# 3-1.net
KiCad netlist of a schematic drawn in Altium Designer
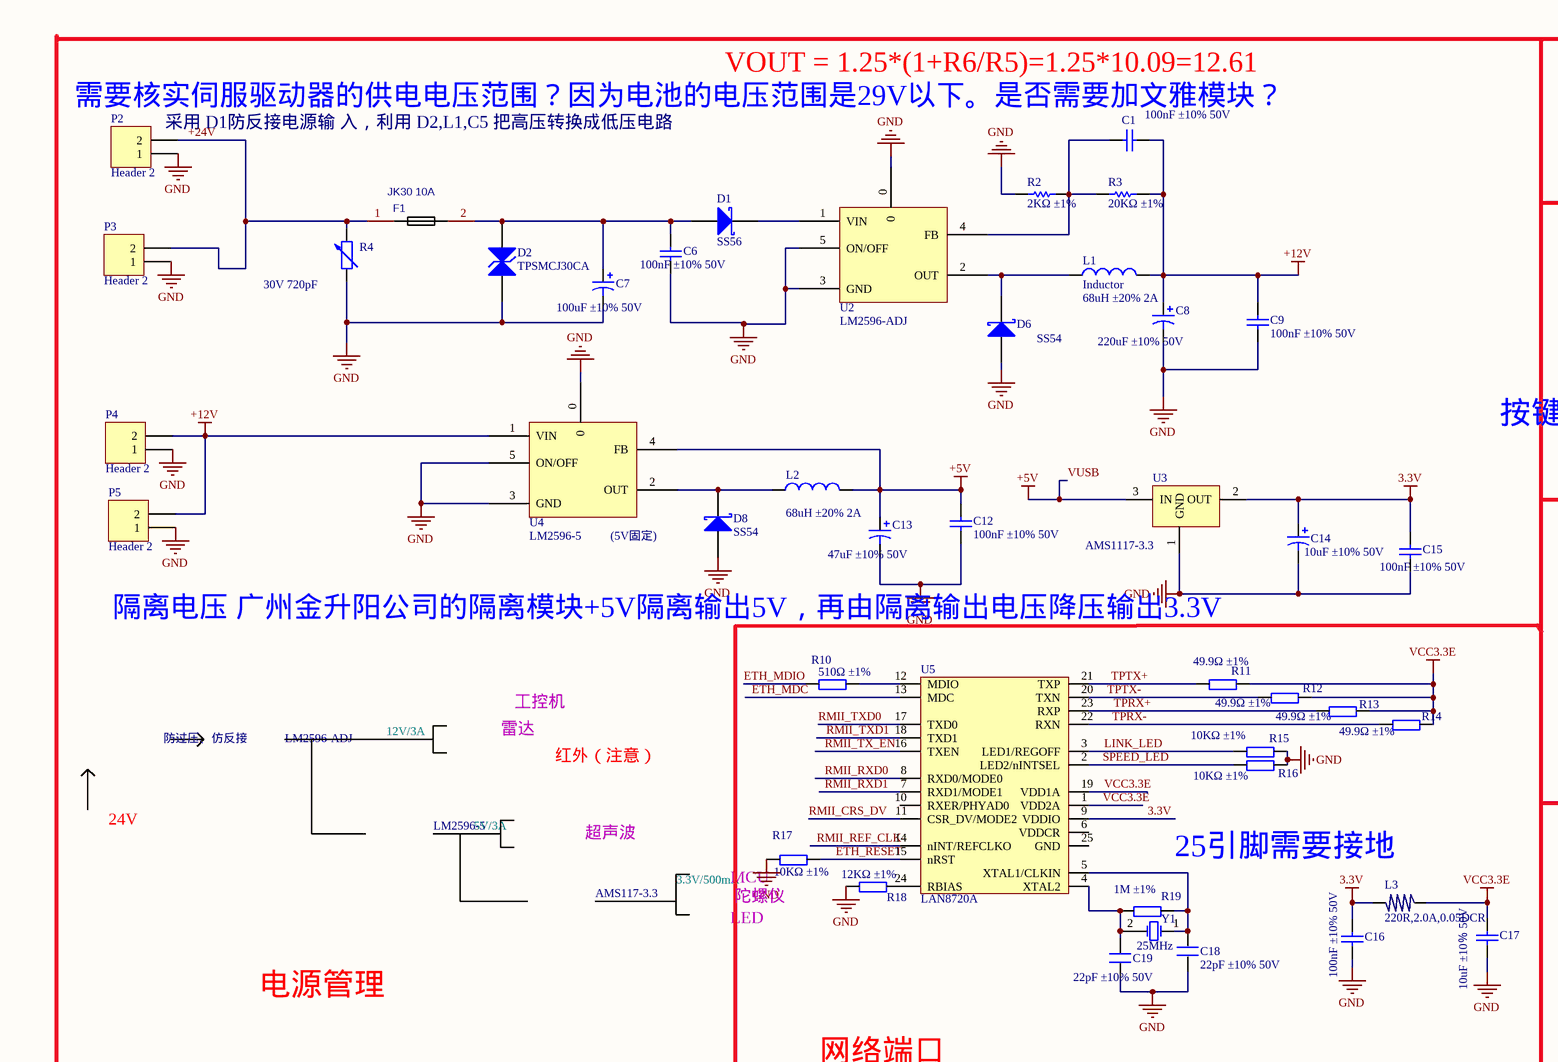
[diagram p0: 运输机器人3-1.SchDoc, top left]
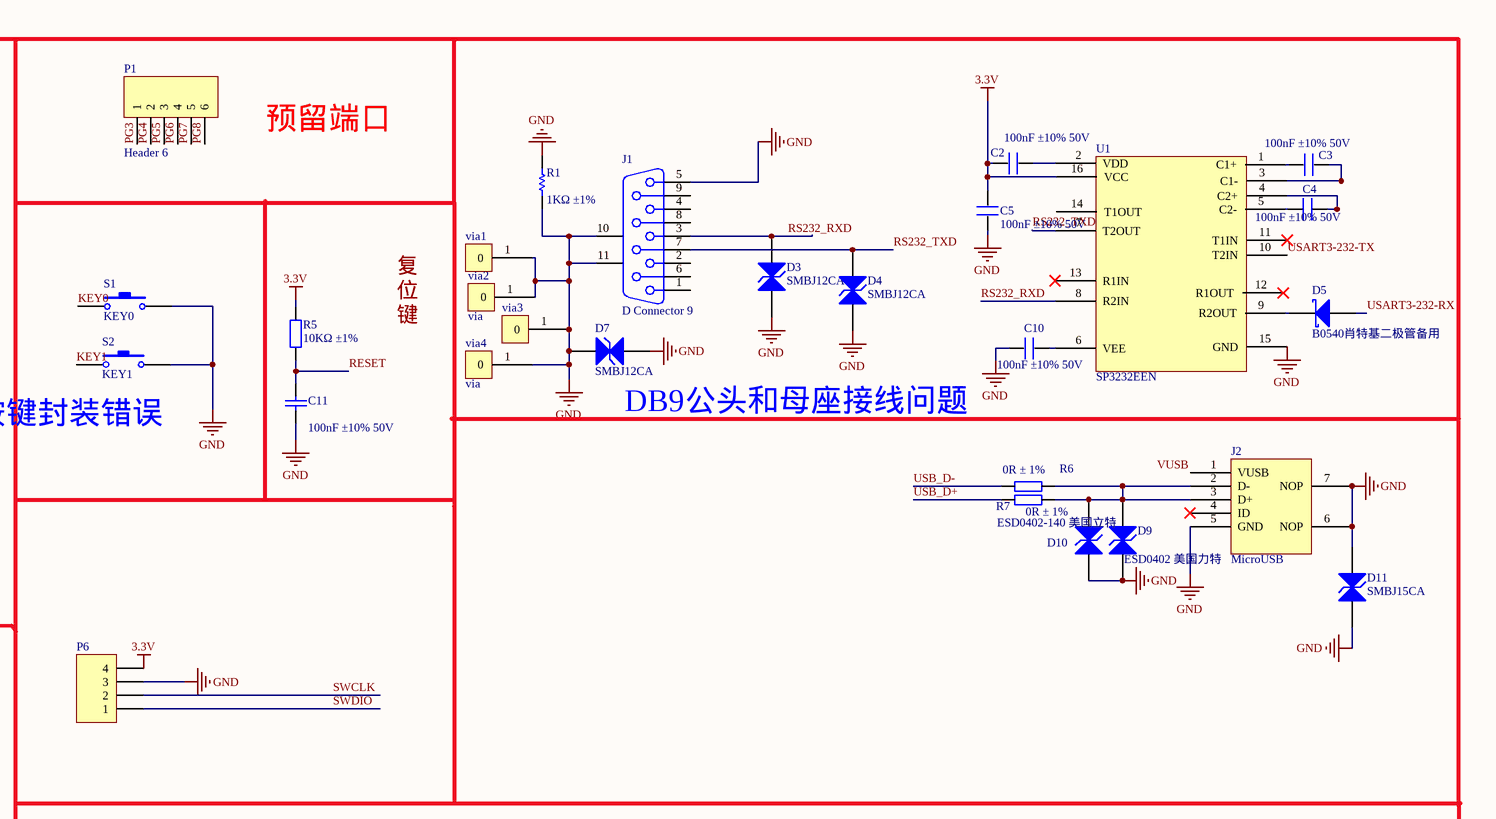
[diagram p1: 运输机器人3-1.SchDoc, top right]
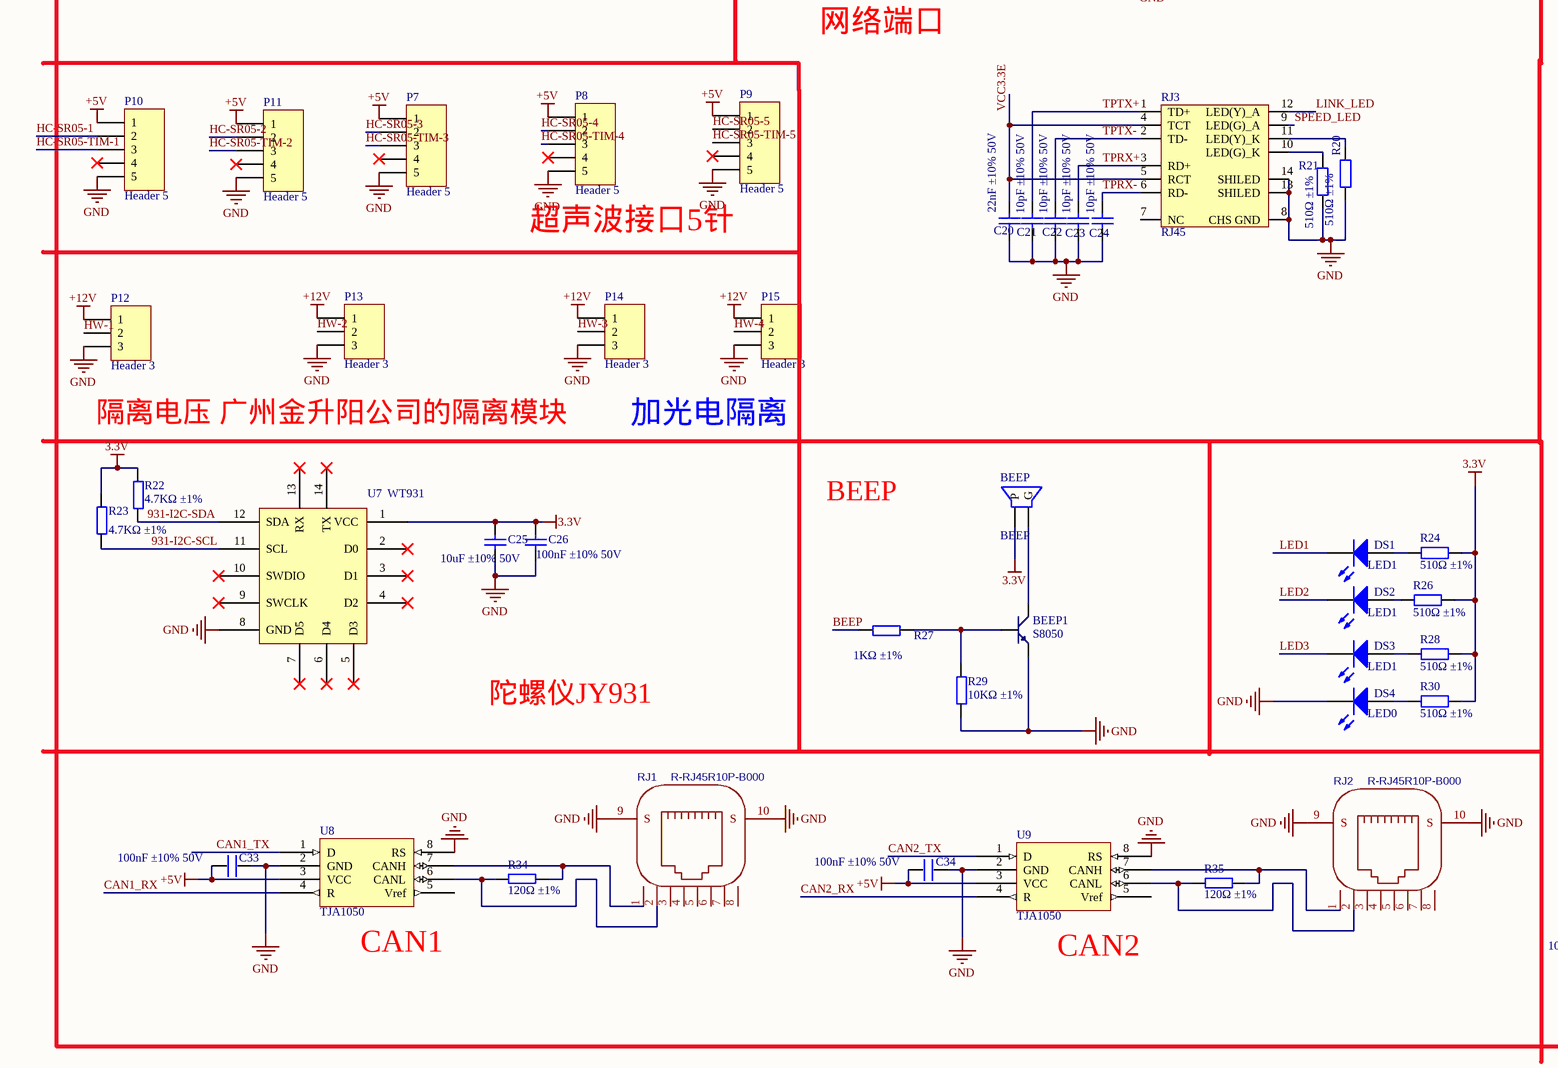
[diagram p2: 运输机器人3-1.SchDoc, bottom left]
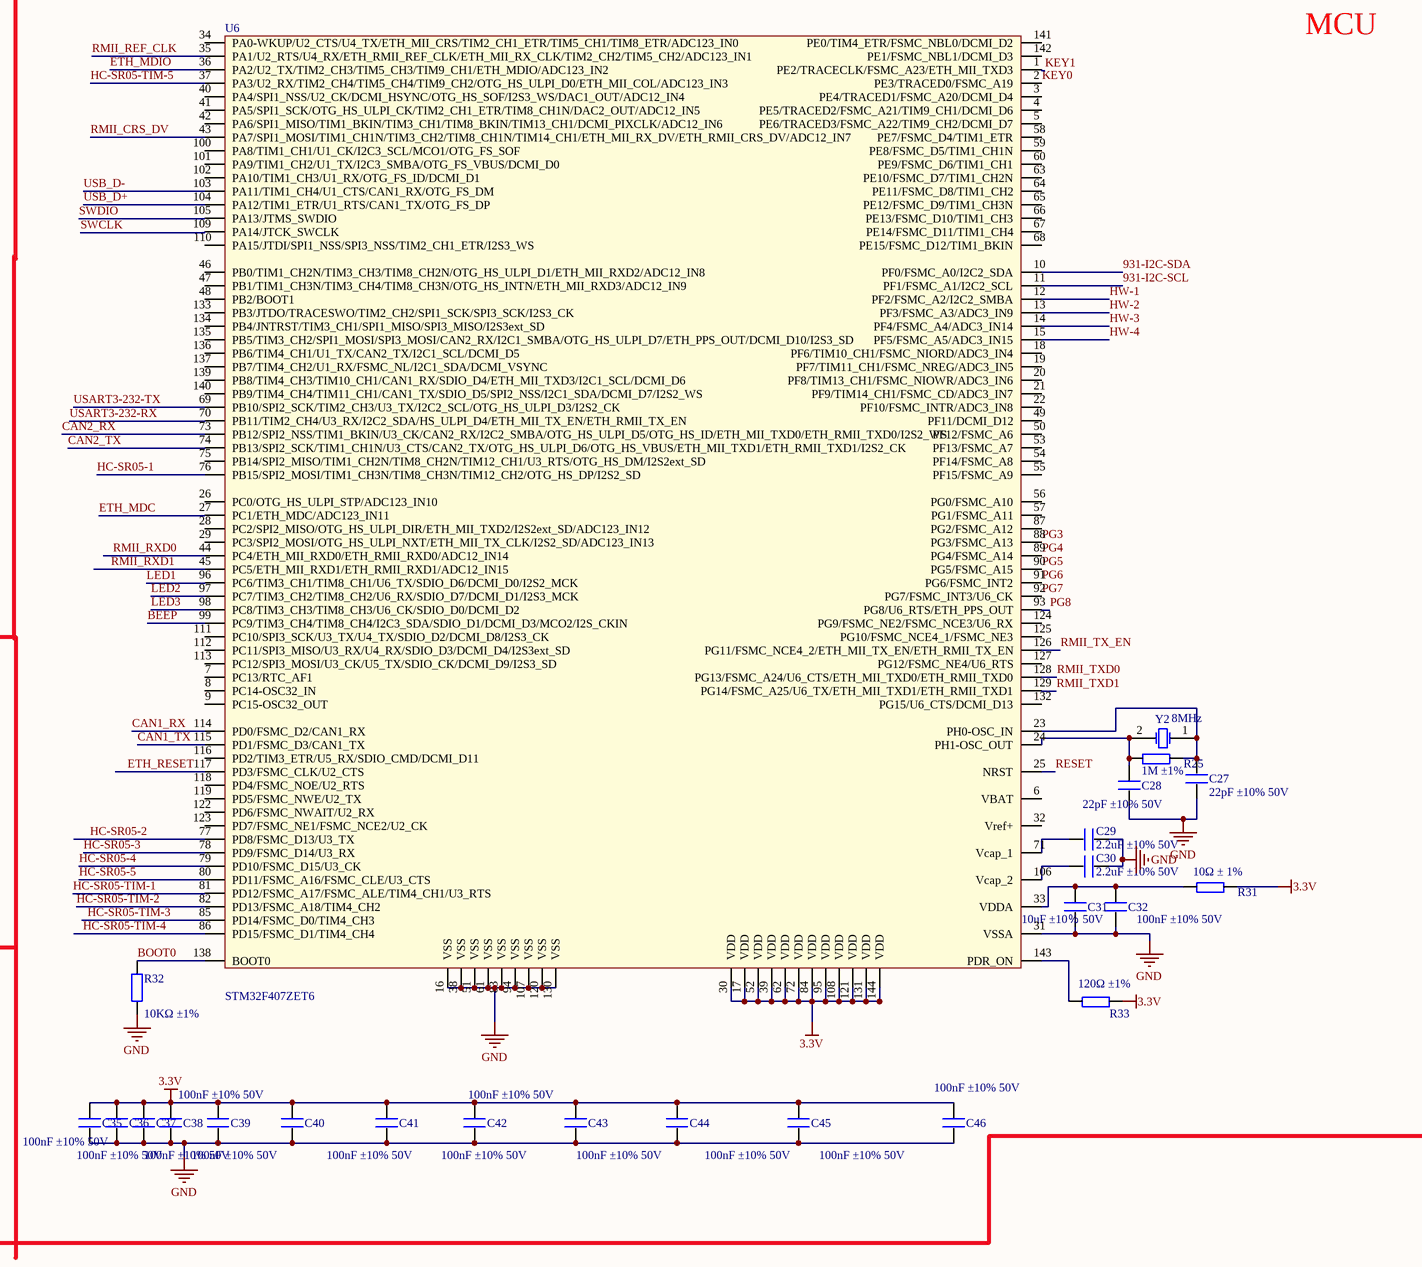
[diagram p3: 运输机器人3-1.SchDoc, bottom right]

(export (version "E")
  (design (tool "Eeschema 10.0.6"))
  (components
    (comp (ref "BEEP")
      (value "BEEP")
      (footprint "LB-BUZ-TH_BD12.0-P7.60-D0.6-FD")
      (libsource (lib "Explorer STM32F407封装库") (part "BEEP"))
    )
    (comp (ref "BEEP1")
      (value "S8050")
      (footprint "LC-SOT-23(SOT-23-3)")
      (description "8050/BCW846/BCW847")
      (libsource (lib "Explorer STM32F407封装库") (part "NPN"))
    )
    (comp (ref "C1")
      (value "100nF ±10% 50V")
      (footprint "LC-0603_C")
      (description "Capacitor")
      (fields (field (name "PUBLISHER") "Altium Limited"))
      (libsource (lib "Miscellaneous Devices") (part "Cap"))
    )
    (comp (ref "C2")
      (value "100nF ±10% 50V")
      (footprint "LC-0603_C")
      (libsource (lib "WarShip V3 STM32103封装库") (part "C"))
    )
    (comp (ref "C3")
      (value "100nF ±10% 50V")
      (footprint "LC-0603_C")
      (libsource (lib "WarShip V3 STM32103封装库") (part "C"))
    )
    (comp (ref "C4")
      (value "100nF ±10% 50V")
      (footprint "LC-0603_C")
      (libsource (lib "WarShip V3 STM32103封装库") (part "C"))
    )
    (comp (ref "C5")
      (value "100nF ±10% 50V")
      (footprint "LC-0603_C")
      (libsource (lib "WarShip V3 STM32103封装库") (part "C"))
    )
    (comp (ref "C6")
      (value "100nF ±10% 50V")
      (footprint "LC-0603_C")
      (description "Capacitor")
      (fields (field (name "PUBLISHER") "Altium Limited"))
      (libsource (lib "Miscellaneous Devices") (part "Cap"))
    )
    (comp (ref "C7")
      (value "100uF ±10% 50V")
      (footprint "C-RB.1/.4 8*12")
      (description "Polarized Capacitor (Radial)")
      (fields (field (name "PUBLISHER") "Altium Limited"))
      (libsource (lib "Miscellaneous Devices") (part "Cap Pol1"))
    )
    (comp (ref "C8")
      (value "220uF ±10% 50V")
      (footprint "C-RB.2/.4 Φ10")
      (description "Polarized Capacitor (Radial)")
      (fields (field (name "PUBLISHER") "Altium Limited"))
      (libsource (lib "Miscellaneous Devices") (part "Cap Pol1"))
    )
    (comp (ref "C9")
      (value "100nF ±10% 50V")
      (footprint "LC-0603_C")
      (description "Capacitor")
      (fields (field (name "PUBLISHER") "Altium Limited"))
      (libsource (lib "Miscellaneous Devices") (part "Cap"))
    )
    (comp (ref "C10")
      (value "100nF ±10% 50V")
      (footprint "LC-0603_C")
      (libsource (lib "WarShip V3 STM32103封装库") (part "C"))
    )
    (comp (ref "C11")
      (value "100nF ±10% 50V")
      (footprint "LC-0603_C")
      (description "Capacitor (Semiconductor SIM Model)")
      (fields (field (name "PUBLISHER") "Altium Limited"))
      (libsource (lib "Miscellaneous Devices") (part "Cap Semi"))
    )
    (comp (ref "C12")
      (value "100nF ±10% 50V")
      (footprint "LC-0603_C")
      (description "Capacitor")
      (fields (field (name "PUBLISHER") "Altium Limited"))
      (libsource (lib "Miscellaneous Devices") (part "Cap"))
    )
    (comp (ref "C13")
      (value "47uF ±10% 50V")
      (footprint "LC-1206_C")
      (description "Polarized Capacitor (Radial)")
      (fields (field (name "PUBLISHER") "Altium Limited"))
      (libsource (lib "Miscellaneous Devices") (part "Cap Pol1"))
    )
    (comp (ref "C14")
      (value "10uF ±10% 50V")
      (footprint "LC-1206_C")
      (description "Polarized Capacitor (Radial)")
      (fields (field (name "PUBLISHER") "Altium Limited"))
      (libsource (lib "Miscellaneous Devices") (part "Cap Pol1"))
    )
    (comp (ref "C15")
      (value "100nF ±10% 50V")
      (footprint "LC-0603_C")
      (description "Capacitor")
      (fields (field (name "PUBLISHER") "Altium Limited"))
      (libsource (lib "Miscellaneous Devices") (part "Cap"))
    )
    (comp (ref "C16")
      (value "100nF ±10% 50V")
      (footprint "LC-0603_C")
      (description "Capacitor")
      (fields (field (name "PUBLISHER") "Altium Limited"))
      (libsource (lib "Miscellaneous Devices") (part "Cap"))
    )
    (comp (ref "C17")
      (value "10uF ±10％ 50V")
      (footprint "LC-1206_C")
      (description "Capacitor")
      (fields (field (name "PUBLISHER") "Altium Limited"))
      (libsource (lib "Miscellaneous Devices") (part "Cap"))
    )
    (comp (ref "C18")
      (value "22pF ±10% 50V")
      (footprint "LC-0603_C")
      (libsource (lib "WarShip V3 STM32103封装库") (part "C"))
    )
    (comp (ref "C19")
      (value "22pF ±10% 50V")
      (footprint "LC-0603_C")
      (libsource (lib "WarShip V3 STM32103封装库") (part "C"))
    )
    (comp (ref "C20")
      (value "22nF ±10% 50V")
      (footprint "LC-0603_C")
      (description "Capacitor")
      (fields (field (name "PUBLISHER") "Altium Limited"))
      (libsource (lib "Miscellaneous Devices") (part "Cap"))
    )
    (comp (ref "C21")
      (value "10pF ±10% 50V")
      (footprint "LC-0603_C")
      (description "Capacitor")
      (fields (field (name "PUBLISHER") "Altium Limited"))
      (libsource (lib "Miscellaneous Devices") (part "Cap"))
    )
    (comp (ref "C22")
      (value "10pF ±10% 50V")
      (footprint "LC-0603_C")
      (description "Capacitor")
      (fields (field (name "PUBLISHER") "Altium Limited"))
      (libsource (lib "Miscellaneous Devices") (part "Cap"))
    )
    (comp (ref "C23")
      (value "10pF ±10% 50V")
      (footprint "LC-0603_C")
      (description "Capacitor")
      (fields (field (name "PUBLISHER") "Altium Limited"))
      (libsource (lib "Miscellaneous Devices") (part "Cap"))
    )
    (comp (ref "C24")
      (value "10pF ±10% 50V")
      (footprint "LC-0603_C")
      (description "Capacitor")
      (fields (field (name "PUBLISHER") "Altium Limited"))
      (libsource (lib "Miscellaneous Devices") (part "Cap"))
    )
    (comp (ref "C25")
      (value "10uF ±10% 50V")
      (footprint "LC-1206_C")
      (description "Capacitor")
      (fields (field (name "PUBLISHER") "Altium Limited"))
      (libsource (lib "Miscellaneous Devices") (part "Cap"))
    )
    (comp (ref "C26")
      (value "100nF ±10% 50V")
      (footprint "LC-0603_C")
      (description "Capacitor")
      (fields (field (name "PUBLISHER") "Altium Limited"))
      (libsource (lib "Miscellaneous Devices") (part "Cap"))
    )
    (comp (ref "C27")
      (value "22pF ±10% 50V")
      (footprint "LC-0603_C")
      (libsource (lib "WarShip V3 STM32103封装库") (part "C"))
    )
    (comp (ref "C28")
      (value "22pF ±10% 50V")
      (footprint "LC-0603_C")
      (libsource (lib "WarShip V3 STM32103封装库") (part "C"))
    )
    (comp (ref "C29")
      (value "2.2uF ±10% 50V")
      (footprint "LC-0603_C")
      (libsource (lib "WarShip V3 STM32103封装库") (part "C"))
    )
    (comp (ref "C30")
      (value "2.2uF ±10% 50V")
      (footprint "LC-0603_C")
      (libsource (lib "WarShip V3 STM32103封装库") (part "C"))
    )
    (comp (ref "C31")
      (value "10uF ±10％ 50V")
      (footprint "LC-1206_C")
      (libsource (lib "WarShip V3 STM32103封装库") (part "C"))
    )
    (comp (ref "C32")
      (value "100nF ±10% 50V")
      (footprint "LC-0603_C")
      (libsource (lib "WarShip V3 STM32103封装库") (part "C"))
    )
    (comp (ref "C33")
      (value "100nF ±10% 50V")
      (footprint "LC-0603_C")
      (libsource (lib "WarShip V3 STM32103封装库") (part "C"))
    )
    (comp (ref "C34")
      (value "100nF ±10% 50V")
      (footprint "LC-0603_C")
      (libsource (lib "WarShip V3 STM32103封装库") (part "C"))
    )
    (comp (ref "C35")
      (value "100nF ±10% 50V")
      (footprint "LC-0603_C")
      (libsource (lib "WarShip V3 STM32103封装库") (part "C"))
    )
    (comp (ref "C36")
      (value "100nF ±10% 50V")
      (footprint "LC-0603_C")
      (libsource (lib "WarShip V3 STM32103封装库") (part "C"))
    )
    (comp (ref "C37")
      (value "100nF ±10% 50V")
      (footprint "LC-0603_C")
      (libsource (lib "WarShip V3 STM32103封装库") (part "C"))
    )
    (comp (ref "C38")
      (value "100nF ±10% 50V")
      (footprint "LC-0603_C")
      (libsource (lib "WarShip V3 STM32103封装库") (part "C"))
    )
    (comp (ref "C39")
      (value "100nF ±10% 50V")
      (footprint "LC-0603_C")
      (libsource (lib "WarShip V3 STM32103封装库") (part "C"))
    )
    (comp (ref "C40")
      (value "100nF ±10% 50V")
      (footprint "LC-0603_C")
      (libsource (lib "WarShip V3 STM32103封装库") (part "C"))
    )
    (comp (ref "C41")
      (value "100nF ±10% 50V")
      (footprint "LC-0603_C")
      (libsource (lib "WarShip V3 STM32103封装库") (part "C"))
    )
    (comp (ref "C42")
      (value "100nF ±10% 50V")
      (footprint "LC-0603_C")
      (libsource (lib "WarShip V3 STM32103封装库") (part "C"))
    )
    (comp (ref "C43")
      (value "100nF ±10% 50V")
      (footprint "LC-0603_C")
      (libsource (lib "WarShip V3 STM32103封装库") (part "C"))
    )
    (comp (ref "C44")
      (value "100nF ±10% 50V")
      (footprint "LC-0603_C")
      (libsource (lib "WarShip V3 STM32103封装库") (part "C"))
    )
    (comp (ref "C45")
      (value "100nF ±10% 50V")
      (footprint "LC-0603_C")
      (libsource (lib "WarShip V3 STM32103封装库") (part "C"))
    )
    (comp (ref "C46")
      (value "100nF ±10% 50V")
      (footprint "LC-0603_C")
      (libsource (lib "WarShip V3 STM32103封装库") (part "C"))
    )
    (comp (ref "D1")
      (value "SS56")
      (footprint "LC-SMC(DO-214AB)_S2")
      (description "Schottky Diode")
      (fields (field (name "PUBLISHER") "Altium Limited"))
      (libsource (lib "Miscellaneous Devices") (part "D Schottky"))
    )
    (comp (ref "D2")
      (value "TPSMCJ30CA")
      (footprint "LC-SMC(DO-214AB)_S4")
      (description "Zener Diode")
      (fields (field (name "PUBLISHER") "Altium Limited"))
      (libsource (lib "*") (part "D Zener"))
    )
    (comp (ref "D3")
      (value "SMBJ12CA")
      (footprint "LC-SMB(DO-214AA)_S4")
      (description "Zener Diode")
      (fields (field (name "PUBLISHER") "Altium Limited"))
      (libsource (lib "Schlib1") (part "D Zener"))
    )
    (comp (ref "D4")
      (value "SMBJ12CA")
      (footprint "LC-SMB(DO-214AA)_S4")
      (description "Zener Diode")
      (fields (field (name "PUBLISHER") "Altium Limited"))
      (libsource (lib "*") (part "D Zener"))
    )
    (comp (ref "D5")
      (value "B0540肖特基二极管备用")
      (footprint "LC-SOD-123")
      (description "Schottky Diode")
      (fields (field (name "PUBLISHER") "Altium Limited"))
      (libsource (lib "Miscellaneous Devices") (part "D Schottky"))
    )
    (comp (ref "D6")
      (value "SS54")
      (footprint "LC-SMB(DO-214AA)_S4")
      (description "Schottky Diode")
      (fields (field (name "PUBLISHER") "Altium Limited"))
      (libsource (lib "Miscellaneous Devices") (part "D Schottky"))
    )
    (comp (ref "D7")
      (value "SMBJ12CA")
      (footprint "LC-SMB(DO-214AA)_S4")
      (description "Zener Diode")
      (fields (field (name "PUBLISHER") "Altium Limited"))
      (libsource (lib "Schlib1") (part "D Zener"))
    )
    (comp (ref "D8")
      (value "SS54")
      (footprint "LC-SMB(DO-214AA)_S4")
      (description "Schottky Diode")
      (fields (field (name "PUBLISHER") "Altium Limited"))
      (libsource (lib "Miscellaneous Devices") (part "D Schottky"))
    )
    (comp (ref "D9")
      (value "ESD0402 美国力特")
      (footprint "LC-0603")
      (description "Zener Diode")
      (fields (field (name "PUBLISHER") "Altium Limited"))
      (libsource (lib "*") (part "D Zener"))
    )
    (comp (ref "D10")
      (value "ESD0402-140 美国立特")
      (footprint "LC-0603")
      (description "Zener Diode")
      (fields (field (name "PUBLISHER") "Altium Limited"))
      (libsource (lib "*") (part "D Zener"))
    )
    (comp (ref "D11")
      (value "SMBJ15CA")
      (footprint "LC-SMB(DO-214AA)_S5")
      (description "Zener Diode")
      (fields (field (name "PUBLISHER") "Altium Limited"))
      (libsource (lib "*") (part "D Zener"))
    )
    (comp (ref "DS1")
      (value "LED1")
      (footprint "LC-0805")
      (description "Typical RED, GREEN, YELLOW, AMBER GaAs LED")
      (fields (field (name "PUBLISHER") "Altium Limited"))
      (libsource (lib "Explorer STM32F407封装库") (part "LED2"))
    )
    (comp (ref "DS2")
      (value "LED1")
      (footprint "LC-0805")
      (description "Typical RED, GREEN, YELLOW, AMBER GaAs LED")
      (fields (field (name "PUBLISHER") "Altium Limited"))
      (libsource (lib "Explorer STM32F407封装库") (part "LED2"))
    )
    (comp (ref "DS3")
      (value "LED1")
      (footprint "LC-0805")
      (description "Typical RED, GREEN, YELLOW, AMBER GaAs LED")
      (fields (field (name "PUBLISHER") "Altium Limited"))
      (libsource (lib "Explorer STM32F407封装库") (part "LED2"))
    )
    (comp (ref "DS4")
      (value "LED0")
      (footprint "LC-0805")
      (description "Typical RED, GREEN, YELLOW, AMBER GaAs LED")
      (fields (field (name "PUBLISHER") "Altium Limited"))
      (libsource (lib "Explorer STM32F407封装库") (part "LED2"))
    )
    (comp (ref "F1")
      (value "JK30 10A")
      (footprint "JK60-110")
      (fields
        (field (name "BOM_MANUFACTURER PART") "Self-healing fuse/HRL30-500")
        (field (name "BOM_SUPPLIER PART") "C14155")
      )
      (libsource (lib "Schlib1") (part "Self-healing fuse/HRL30-500"))
    )
    (comp (ref "J1")
      (value "D Connector 9")
      (footprint "LB-DSUB-TH_DMR-9P")
      (description "Receptacle Assembly, 9 Position, Right Angle")
      (fields (field (name "PUBLISHER") "Altium Limited"))
      (libsource (lib "Miscellaneous Connectors") (part "D Connector 9"))
    )
    (comp (ref "J2")
      (value "MicroUSB")
      (footprint "MicroUSB - 牛角无边")
      (libsource (lib "Motion Controller") (part "MicroUSB"))
    )
    (comp (ref "L1")
      (value "Inductor")
      (footprint "SMDRH63")
      (fields (field (name "ALTIUM_VALUE") "68uH ±20% 2A") (field (name "PUBLISHER") "Altium Limited"))
      (libsource (lib "Miscellaneous Devices") (part "Inductor"))
    )
    (comp (ref "L2")
      (value "68uH ±20% 2A")
      (footprint "SMDRH63")
      (description "Inductor")
      (fields (field (name "PUBLISHER") "Altium Limited"))
      (libsource (lib "Miscellaneous Devices") (part "Inductor"))
    )
    (comp (ref "L3")
      (value "220R,2.0A,0.05DCR")
      (footprint "LC-0805_L")
      (libsource (lib "Explorer STM32F407封装库") (part "L"))
    )
    (comp (ref "P1")
      (value "Header 6")
      (footprint "HDR1X6")
      (description "Header, 6-Pin")
      (fields (field (name "PUBLISHER") "Altium Limited"))
      (libsource (lib "Miscellaneous Connectors") (part "Header 6"))
    )
    (comp (ref "P2")
      (value "Header 2")
      (footprint "LB-XT60PW")
      (description "Header, 2-Pin")
      (fields (field (name "PUBLISHER") "Altium Limited"))
      (libsource (lib "Miscellaneous Connectors") (part "Header 2"))
    )
    (comp (ref "P3")
      (value "Header 2")
      (footprint "LB-XT60PW")
      (description "Header, 2-Pin")
      (fields (field (name "PUBLISHER") "Altium Limited"))
      (libsource (lib "Miscellaneous Connectors") (part "Header 2"))
    )
    (comp (ref "P4")
      (value "Header 2")
      (footprint "LB-CONN-TH_2P-P5.08_WJ2EDGRC-5.08-2P")
      (description "Header, 2-Pin")
      (fields (field (name "PUBLISHER") "Altium Limited"))
      (libsource (lib "Miscellaneous Connectors") (part "Header 2"))
    )
    (comp (ref "P5")
      (value "Header 2")
      (footprint "LB-CONN-TH_2P-P5.08_WJ2EDGRC-5.08-2P")
      (description "Header, 2-Pin")
      (fields (field (name "PUBLISHER") "Altium Limited"))
      (libsource (lib "Miscellaneous Connectors") (part "Header 2"))
    )
    (comp (ref "P6")
      (value "Header 4")
      (footprint "HDR1X4")
      (description "Header, 4-Pin")
      (fields (field (name "PUBLISHER") "Altium Limited"))
      (libsource (lib "mcumotor") (part "Header 4"))
    )
    (comp (ref "P7")
      (value "Header 5")
      (footprint "LB-CONN-TH_5P-P2.50_X8821WR-05S-N0SN")
      (description "Header, 5-Pin")
      (fields (field (name "PUBLISHER") "Altium Limited"))
      (libsource (lib "Miscellaneous Connectors") (part "Header 5"))
    )
    (comp (ref "P8")
      (value "Header 5")
      (footprint "LB-CONN-TH_5P-P2.50_X8821WR-05S-N0SN")
      (description "Header, 5-Pin")
      (fields (field (name "PUBLISHER") "Altium Limited"))
      (libsource (lib "Miscellaneous Connectors") (part "Header 5"))
    )
    (comp (ref "P9")
      (value "Header 5")
      (footprint "LB-CONN-TH_5P-P2.50_X8821WR-05S-N0SN")
      (description "Header, 5-Pin")
      (fields (field (name "PUBLISHER") "Altium Limited"))
      (libsource (lib "Miscellaneous Connectors") (part "Header 5"))
    )
    (comp (ref "P10")
      (value "Header 5")
      (footprint "LB-CONN-TH_5P-P2.50_X8821WR-05S-N0SN")
      (description "Header, 5-Pin")
      (fields (field (name "PUBLISHER") "Altium Limited"))
      (libsource (lib "Miscellaneous Connectors") (part "Header 5"))
    )
    (comp (ref "P11")
      (value "Header 5")
      (footprint "LB-CONN-TH_5P-P2.50_X8821WR-05S-N0SN")
      (description "Header, 5-Pin")
      (fields (field (name "PUBLISHER") "Altium Limited"))
      (libsource (lib "Miscellaneous Connectors") (part "Header 5"))
    )
    (comp (ref "P12")
      (value "Header 3")
      (footprint "LB-CONN-TH_3P-P2.50_X8821WR-03S-N0SN")
      (description "Header, 3-Pin")
      (fields (field (name "PUBLISHER") "Altium Limited"))
      (libsource (lib "Miscellaneous Connectors") (part "Header 3"))
    )
    (comp (ref "P13")
      (value "Header 3")
      (footprint "LB-CONN-TH_3P-P2.50_X8821WR-03S-N0SN")
      (description "Header, 3-Pin")
      (fields (field (name "PUBLISHER") "Altium Limited"))
      (libsource (lib "Miscellaneous Connectors") (part "Header 3"))
    )
    (comp (ref "P14")
      (value "Header 3")
      (footprint "LB-CONN-TH_3P-P2.50_X8821WR-03S-N0SN")
      (description "Header, 3-Pin")
      (fields (field (name "PUBLISHER") "Altium Limited"))
      (libsource (lib "Miscellaneous Connectors") (part "Header 3"))
    )
    (comp (ref "P15")
      (value "Header 3")
      (footprint "LB-CONN-TH_3P-P2.50_X8821WR-03S-N0SN")
      (description "Header, 3-Pin")
      (fields (field (name "PUBLISHER") "Altium Limited"))
      (libsource (lib "Miscellaneous Connectors") (part "Header 3"))
    )
    (comp (ref "R1")
      (value "1KΩ ±1%")
      (footprint "LC-0603_R")
      (description "Resistor")
      (fields (field (name "PUBLISHER") "Altium Limited"))
      (libsource (lib "Miscellaneous Devices") (part "Res1"))
    )
    (comp (ref "R2")
      (value "2KΩ ±1%")
      (footprint "LC-0603_R")
      (description "Resistor")
      (fields (field (name "PUBLISHER") "Altium Limited"))
      (libsource (lib "Miscellaneous Devices") (part "Res1"))
    )
    (comp (ref "R3")
      (value "20KΩ ±1%")
      (footprint "LC-0603_R")
      (description "Resistor")
      (fields (field (name "PUBLISHER") "Altium Limited"))
      (libsource (lib "Miscellaneous Devices") (part "Res1"))
    )
    (comp (ref "R4")
      (value "30V 720pF")
      (footprint "R-7.5")
      (description "Variable Resistor")
      (fields (field (name "PUBLISHER") "Altium Limited"))
      (libsource (lib "Miscellaneous Devices") (part "Res Adj2"))
    )
    (comp (ref "R5")
      (value "10KΩ ±1%")
      (footprint "LC-0603_R")
      (description "贴片电阻")
      (fields (field (name "版权归属") "源创客"))
      (libsource (lib "PCB_Project1") (part "R"))
    )
    (comp (ref "R6")
      (value "0R ± 1%")
      (footprint "LC-0603_R")
      (libsource (lib "WarShip V3 STM32103封装库") (part "R"))
    )
    (comp (ref "R7")
      (value "0R ± 1%")
      (footprint "LC-0603_R")
      (libsource (lib "WarShip V3 STM32103封装库") (part "R"))
    )
    (comp (ref "R10")
      (value "510Ω ±1%")
      (footprint "LC-0603_R")
      (libsource (lib "WarShip V3 STM32103封装库") (part "R"))
    )
    (comp (ref "R11")
      (value "49.9Ω ±1%")
      (footprint "LC-0603_R")
      (libsource (lib "WarShip V3 STM32103封装库") (part "R"))
    )
    (comp (ref "R12")
      (value "49.9Ω ±1%")
      (footprint "LC-0603_R")
      (libsource (lib "WarShip V3 STM32103封装库") (part "R"))
    )
    (comp (ref "R13")
      (value "49.9Ω ±1%")
      (footprint "LC-0603_R")
      (libsource (lib "WarShip V3 STM32103封装库") (part "R"))
    )
    (comp (ref "R14")
      (value "49.9Ω ±1%")
      (footprint "LC-0603_R")
      (libsource (lib "WarShip V3 STM32103封装库") (part "R"))
    )
    (comp (ref "R15")
      (value "10KΩ ±1%")
      (footprint "LC-0603_R")
      (libsource (lib "WarShip V3 STM32103封装库") (part "R"))
    )
    (comp (ref "R16")
      (value "10KΩ ±1%")
      (footprint "LC-0603_R")
      (libsource (lib "WarShip V3 STM32103封装库") (part "R"))
    )
    (comp (ref "R17")
      (value "10KΩ ±1%")
      (footprint "LC-0603_R")
      (libsource (lib "WarShip V3 STM32103封装库") (part "R"))
    )
    (comp (ref "R18")
      (value "12KΩ ±1%")
      (footprint "LC-0603_R")
      (libsource (lib "WarShip V3 STM32103封装库") (part "R"))
    )
    (comp (ref "R19")
      (value "1M ±1%")
      (footprint "LC-0603_R")
      (libsource (lib "WarShip V3 STM32103封装库") (part "R"))
    )
    (comp (ref "R20")
      (value "510Ω ±1%")
      (footprint "LC-0603_R")
      (description "贴片电阻")
      (fields (field (name "版权归属") "源创客"))
      (libsource (lib "PCB_Project1") (part "R"))
    )
    (comp (ref "R21")
      (value "510Ω ±1%")
      (footprint "LC-0603_R")
      (description "贴片电阻")
      (fields (field (name "版权归属") "源创客"))
      (libsource (lib "PCB_Project1") (part "R"))
    )
    (comp (ref "R22")
      (value "4.7KΩ ±1%")
      (footprint "LC-0603_R")
      (libsource (lib "WarShip V3 STM32103封装库") (part "R"))
    )
    (comp (ref "R23")
      (value "4.7KΩ ±1%")
      (footprint "LC-0603_R")
      (libsource (lib "WarShip V3 STM32103封装库") (part "R"))
    )
    (comp (ref "R24")
      (value "510Ω ±1%")
      (footprint "LC-0603_R")
      (description "贴片电阻")
      (fields (field (name "版权归属") "源创客"))
      (libsource (lib "PCB_Project1") (part "R"))
    )
    (comp (ref "R25")
      (value "1M ±1%")
      (footprint "LC-0603_R")
      (libsource (lib "WarShip V3 STM32103封装库") (part "R"))
    )
    (comp (ref "R26")
      (value "510Ω ±1%")
      (footprint "LC-0603_R")
      (description "贴片电阻")
      (fields (field (name "版权归属") "源创客"))
      (libsource (lib "PCB_Project1") (part "R"))
    )
    (comp (ref "R27")
      (value "1KΩ ±1%")
      (footprint "LC-0603_R")
      (libsource (lib "WarShip V3 STM32103封装库") (part "R"))
    )
    (comp (ref "R28")
      (value "510Ω ±1%")
      (footprint "LC-0603_R")
      (description "贴片电阻")
      (fields (field (name "版权归属") "源创客"))
      (libsource (lib "PCB_Project1") (part "R"))
    )
    (comp (ref "R29")
      (value "10KΩ ±1%")
      (footprint "LC-0603_R")
      (libsource (lib "WarShip V3 STM32103封装库") (part "R"))
    )
    (comp (ref "R30")
      (value "510Ω ±1%")
      (footprint "LC-0603_R")
      (description "贴片电阻")
      (fields (field (name "版权归属") "源创客"))
      (libsource (lib "PCB_Project1") (part "R"))
    )
    (comp (ref "R31")
      (value "10Ω ± 1%")
      (footprint "LC-0603_R")
      (libsource (lib "WarShip V3 STM32103封装库") (part "R"))
    )
    (comp (ref "R32")
      (value "10KΩ ±1%")
      (footprint "LC-0603_R")
      (description "贴片电阻")
      (fields (field (name "版权归属") "源创客"))
      (libsource (lib "PCB_Project1") (part "R"))
    )
    (comp (ref "R33")
      (value "120Ω ±1%")
      (footprint "LC-0603_R")
      (libsource (lib "WarShip V3 STM32103封装库") (part "R"))
    )
    (comp (ref "R34")
      (value "120Ω ±1%")
      (footprint "LC-0603_R")
      (libsource (lib "WarShip V3 STM32103封装库") (part "R"))
    )
    (comp (ref "R35")
      (value "120Ω ±1%")
      (footprint "LC-0603_R")
      (libsource (lib "WarShip V3 STM32103封装库") (part "R"))
    )
    (comp (ref "RJ1")
      (value "R-RJ45R10P-B000")
      (footprint "LB-RJ45-TH_R-RJ45R10P-B000")
      (fields (field (name "BOM_SUPPLIER PART") "C386758") (field (name "CONTRIBUTOR") "LCSC"))
      (libsource (lib "Schlib1") (part "R-RJ45R10P-B000"))
    )
    (comp (ref "RJ2")
      (value "R-RJ45R10P-B000")
      (footprint "LB-RJ45-TH_R-RJ45R10P-B000")
      (fields (field (name "BOM_SUPPLIER PART") "C386758") (field (name "CONTRIBUTOR") "LCSC"))
      (libsource (lib "Schlib1") (part "R-RJ45R10P-B000"))
    )
    (comp (ref "RJ3")
      (value "RJ45")
      (footprint "LB-HR911105A")
      (libsource (lib "Explorer STM32F407封装库") (part "HR911105"))
    )
    (comp (ref "S1")
      (value "KEY0")
      (footprint "LB-SW-TH_4P-L6.0-W6.0-P4.50-LS6.5")
      (description "Switch")
      (fields (field (name "PUBLISHER") "Altium Limited"))
      (libsource (lib "Miscellaneous Devices") (part "SW-PB"))
    )
    (comp (ref "S2")
      (value "KEY1")
      (footprint "LB-SW-TH_4P-L6.0-W6.0-P4.50-LS6.5")
      (description "Switch")
      (fields (field (name "PUBLISHER") "Altium Limited"))
      (libsource (lib "Miscellaneous Devices") (part "SW-PB"))
    )
    (comp (ref "U1")
      (value "SP3232EEN")
      (footprint "LC-SOIC-16_150mil")
      (libsource (lib "Schlib1") (part "SP3232EEN"))
    )
    (comp (ref "U2")
      (value "LM2596-ADJ")
      (footprint "LC-TO-263-5")
      (libsource (lib "伦库") (part "LM2596-ADJ"))
    )
    (comp (ref "U3")
      (value "AMS1117-3.3")
      (footprint "LC-SOT-223")
      (libsource (lib "mcumotor") (part "LM1084"))
    )
    (comp (ref "U4") (value "LM2596-5") (footprint "LC-TO-263-5") (libsource (lib "伦库") (part "LM2596-ADJ")))
    (comp (ref "U5")
      (value "LAN8720A")
      (footprint "LC-QFN-24_4x4x05P")
      (description "ETH PHY")
      (libsource (lib "Explorer STM32F407封装库") (part "LAN8720"))
    )
    (comp (ref "U6")
      (value "STM32F407ZET6")
      (footprint "LC-LQFP-144_20x20x05P")
      (libsource (lib "Explorer STM32F407封装库") (part "STM32F407ZET6"))
    )
    (comp (ref "U7") (value "WT931") (footprint "LB-WT931") (libsource (lib "Schlib1") (part "WT931")))
    (comp (ref "U8")
      (value "TJA1050")
      (footprint "LC-SOIC-8_150mil")
      (libsource (lib "WarShip V3 STM32103封装库") (part "SN65HVD230D"))
    )
    (comp (ref "U9")
      (value "TJA1050")
      (footprint "LC-SOIC-8_150mil")
      (libsource (lib "WarShip V3 STM32103封装库") (part "SN65HVD230D"))
    )
    (comp (ref "via1") (value "via") (footprint "hole") (libsource (lib "Schlib1") (part "via")))
    (comp (ref "via2") (value "via") (footprint "hole") (libsource (lib "Schlib1") (part "via")))
    (comp (ref "via3") (value "via") (footprint "hole") (libsource (lib "Schlib1") (part "via")))
    (comp (ref "via4") (value "via") (footprint "hole") (libsource (lib "Schlib1") (part "via")))
    (comp (ref "Y1")
      (value "25MHz")
      (footprint "LC-HC-49S")
      (description "Crystal Oscillator")
      (fields (field (name "PUBLISHER") "Altium Limited"))
      (libsource (lib "Explorer STM32F407封装库") (part "XTAL"))
    )
    (comp (ref "Y2")
      (value "8MHz")
      (footprint "LC-HC-49S")
      (description "Crystal Oscillator")
      (fields (field (name "PUBLISHER") "Altium Limited"))
      (libsource (lib "Explorer STM32F407封装库") (part "XTAL"))
    )
  )
  (nets
    (net (code "1") (name "+5V") (class "Default")
      (node (ref "C12") (pin "2") (pinfunction "2_2") (pintype "passive"))
      (node (ref "C13") (pin "1") (pinfunction "1_1") (pintype "passive"))
      (node (ref "C33") (pin "1") (pintype "passive"))
      (node (ref "C34") (pin "1") (pintype "passive"))
      (node (ref "J2") (pin "1") (pinfunction "VUSB_1") (pintype "passive"))
      (node (ref "L2") (pin "2") (pinfunction "2_2") (pintype "passive"))
      (node (ref "P10") (pin "1") (pinfunction "1_1") (pintype "passive"))
      (node (ref "P11") (pin "1") (pinfunction "1_1") (pintype "passive"))
      (node (ref "P7") (pin "1") (pinfunction "1_1") (pintype "passive"))
      (node (ref "P8") (pin "1") (pinfunction "1_1") (pintype "passive"))
      (node (ref "P9") (pin "1") (pinfunction "1_1") (pintype "passive"))
      (node (ref "U3") (pin "3") (pinfunction "IN_3") (pintype "passive"))
      (node (ref "U4") (pin "4") (pinfunction "FB_4") (pintype "passive"))
      (node (ref "U8") (pin "3") (pinfunction "VCC_3") (pintype "power_in"))
      (node (ref "U9") (pin "3") (pinfunction "VCC_3") (pintype "power_in"))
    )
    (net (code "2") (name "+12V") (class "Default")
      (node (ref "C1") (pin "2") (pinfunction "2_2") (pintype "passive"))
      (node (ref "C8") (pin "1") (pinfunction "1_1") (pintype "passive"))
      (node (ref "C9") (pin "2") (pinfunction "2_2") (pintype "passive"))
      (node (ref "L1") (pin "2") (pinfunction "2_2") (pintype "passive"))
      (node (ref "P12") (pin "1") (pinfunction "1_1") (pintype "passive"))
      (node (ref "P13") (pin "1") (pinfunction "1_1") (pintype "passive"))
      (node (ref "P14") (pin "1") (pinfunction "1_1") (pintype "passive"))
      (node (ref "P15") (pin "1") (pinfunction "1_1") (pintype "passive"))
      (node (ref "P4") (pin "2") (pinfunction "2_2") (pintype "passive"))
      (node (ref "P5") (pin "2") (pinfunction "2_2") (pintype "passive"))
      (node (ref "R3") (pin "2") (pinfunction "2_2") (pintype "passive"))
      (node (ref "U4") (pin "1") (pinfunction "VIN_1") (pintype "passive"))
    )
    (net (code "3") (name "/+24V") (class "Default")
      (node (ref "F1") (pin "1") (pinfunction "1_1") (pintype "passive"))
      (node (ref "P2") (pin "2") (pinfunction "2_2") (pintype "passive"))
      (node (ref "P3") (pin "2") (pinfunction "2_2") (pintype "passive"))
      (node (ref "R4") (pin "2") (pinfunction "2_2") (pintype "passive"))
    )
    (net (code "4") (name "/931-I2C-SCL") (class "Default")
      (node (ref "R23") (pin "1") (pintype "passive"))
      (node (ref "U6") (pin "11") (pinfunction "PF1/FSMC_A1/I2C2_SCL_11") (pintype "passive"))
      (node (ref "U7") (pin "11") (pinfunction "SCL_11") (pintype "passive"))
    )
    (net (code "5") (name "/931-I2C-SDA") (class "Default")
      (node (ref "R22") (pin "1") (pintype "passive"))
      (node (ref "U6") (pin "10") (pinfunction "PF0/FSMC_A0/I2C2_SDA_10") (pintype "passive"))
      (node (ref "U7") (pin "12") (pinfunction "SDA_12") (pintype "passive"))
    )
    (net (code "6") (name "/BEEP") (class "Default")
      (node (ref "R27") (pin "1") (pintype "passive"))
      (node (ref "U6") (pin "99") (pinfunction "PC9/TIM3_CH4/TIM8_CH4/I2C3_SDA/SDIO_D1/DCMI_D3/MCO2/I2S_CKIN_99") (pintype "passive"))
    )
    (net (code "7") (name "/BOOT0") (class "Default")
      (node (ref "R32") (pin "2") (pinfunction "2_2") (pintype "passive"))
      (node (ref "U6") (pin "138") (pinfunction "BOOT0_138") (pintype "passive"))
    )
    (net (code "8") (name "/CAN1_RX") (class "Default")
      (node (ref "U6") (pin "114") (pinfunction "PD0/FSMC_D2/CAN1_RX_114") (pintype "passive"))
      (node (ref "U8") (pin "4") (pinfunction "R_4") (pintype "output"))
    )
    (net (code "9") (name "/CAN1_TX") (class "Default")
      (node (ref "U6") (pin "115") (pinfunction "PD1/FSMC_D3/CAN1_TX_115") (pintype "passive"))
      (node (ref "U8") (pin "1") (pinfunction "D_1") (pintype "input"))
    )
    (net (code "10") (name "/CAN2_RX") (class "Default")
      (node (ref "U6") (pin "73") (pinfunction "PB12/SPI2_NSS/TIM1_BKIN/U3_CK/CAN2_RX/I2C2_SMBA/OTG_HS_ULPI_D5/OTG_HS_ID/ETH_MII_TXD0/ETH_RMII_TXD0/I2S2_WS_73") (pintype "passive"))
      (node (ref "U9") (pin "4") (pinfunction "R_4") (pintype "output"))
    )
    (net (code "11") (name "/CAN2_TX") (class "Default")
      (node (ref "U6") (pin "74") (pinfunction "PB13/SPI2_SCK/TIM1_CH1N/U3_CTS/CAN2_TX/OTG_HS_ULPI_D6/OTG_HS_VBUS/ETH_MII_TXD1/ETH_RMII_TXD1/I2S2_CK_74") (pintype "passive"))
      (node (ref "U9") (pin "1") (pinfunction "D_1") (pintype "input"))
    )
    (net (code "12") (name "/ETH_MDC") (class "Default")
      (node (ref "U5") (pin "13") (pinfunction "MDC_13") (pintype "passive"))
      (node (ref "U6") (pin "27") (pinfunction "PC1/ETH_MDC/ADC123_IN11_27") (pintype "passive"))
    )
    (net (code "13") (name "/ETH_MDIO") (class "Default")
      (node (ref "R10") (pin "1") (pintype "passive"))
      (node (ref "U6") (pin "36") (pinfunction "PA2/U2_TX/TIM2_CH3/TIM5_CH3/TIM9_CH1/ETH_MDIO/ADC123_IN2_36") (pintype "passive"))
    )
    (net (code "14") (name "/ETH_RESET") (class "Default")
      (node (ref "R17") (pin "2") (pintype "passive"))
      (node (ref "U5") (pin "15") (pinfunction "nRST_15") (pintype "passive"))
      (node (ref "U6") (pin "117") (pinfunction "PD3/FSMC_CLK/U2_CTS_117") (pintype "passive"))
    )
    (net (code "15") (name "/HC-SR05-1") (class "Default")
      (node (ref "P10") (pin "2") (pinfunction "2_2") (pintype "passive"))
      (node (ref "U6") (pin "76") (pinfunction "PB15/SPI2_MOSI/TIM1_CH3N/TIM8_CH3N/TIM12_CH2/OTG_HS_DP/I2S2_SD_76") (pintype "passive"))
    )
    (net (code "16") (name "/HC-SR05-2") (class "Default")
      (node (ref "P11") (pin "2") (pinfunction "2_2") (pintype "passive"))
      (node (ref "U6") (pin "77") (pinfunction "PD8/FSMC_D13/U3_TX_77") (pintype "passive"))
    )
    (net (code "17") (name "/HC-SR05-3") (class "Default")
      (node (ref "P7") (pin "2") (pinfunction "2_2") (pintype "passive"))
      (node (ref "U6") (pin "78") (pinfunction "PD9/FSMC_D14/U3_RX_78") (pintype "passive"))
    )
    (net (code "18") (name "/HC-SR05-4") (class "Default")
      (node (ref "P8") (pin "2") (pinfunction "2_2") (pintype "passive"))
      (node (ref "U6") (pin "79") (pinfunction "PD10/FSMC_D15/U3_CK_79") (pintype "passive"))
    )
    (net (code "19") (name "/HC-SR05-5") (class "Default")
      (node (ref "P9") (pin "2") (pinfunction "2_2") (pintype "passive"))
      (node (ref "U6") (pin "80") (pinfunction "PD11/FSMC_A16/FSMC_CLE/U3_CTS_80") (pintype "passive"))
    )
    (net (code "20") (name "/HC-SR05-TIM-1") (class "Default")
      (node (ref "P10") (pin "3") (pinfunction "3_3") (pintype "passive"))
      (node (ref "U6") (pin "81") (pinfunction "PD12/FSMC_A17/FSMC_ALE/TIM4_CH1/U3_RTS_81") (pintype "passive"))
    )
    (net (code "21") (name "/HC-SR05-TIM-2") (class "Default")
      (node (ref "P11") (pin "3") (pinfunction "3_3") (pintype "passive"))
      (node (ref "U6") (pin "82") (pinfunction "PD13/FSMC_A18/TIM4_CH2_82") (pintype "passive"))
    )
    (net (code "22") (name "/HC-SR05-TIM-3") (class "Default")
      (node (ref "P7") (pin "3") (pinfunction "3_3") (pintype "passive"))
      (node (ref "U6") (pin "85") (pinfunction "PD14/FSMC_D0/TIM4_CH3_85") (pintype "passive"))
    )
    (net (code "23") (name "/HC-SR05-TIM-4") (class "Default")
      (node (ref "P8") (pin "3") (pinfunction "3_3") (pintype "passive"))
      (node (ref "U6") (pin "86") (pinfunction "PD15/FSMC_D1/TIM4_CH4_86") (pintype "passive"))
    )
    (net (code "24") (name "/HC-SR05-TIM-5") (class "Default")
      (node (ref "P9") (pin "3") (pinfunction "3_3") (pintype "passive"))
      (node (ref "U6") (pin "37") (pinfunction "PA3/U2_RX/TIM2_CH4/TIM5_CH4/TIM9_CH2/OTG_HS_ULPI_D0/ETH_MII_COL/ADC123_IN3_37") (pintype "passive"))
    )
    (net (code "25") (name "/HW-1") (class "Default")
      (node (ref "P12") (pin "2") (pinfunction "2_2") (pintype "passive"))
      (node (ref "U6") (pin "12") (pinfunction "PF2/FSMC_A2/I2C2_SMBA_12") (pintype "passive"))
    )
    (net (code "26") (name "/HW-2") (class "Default")
      (node (ref "P13") (pin "2") (pinfunction "2_2") (pintype "passive"))
      (node (ref "U6") (pin "13") (pinfunction "PF3/FSMC_A3/ADC3_IN9_13") (pintype "passive"))
    )
    (net (code "27") (name "/HW-3") (class "Default")
      (node (ref "P14") (pin "2") (pinfunction "2_2") (pintype "passive"))
      (node (ref "U6") (pin "14") (pinfunction "PF4/FSMC_A4/ADC3_IN14_14") (pintype "passive"))
    )
    (net (code "28") (name "/HW-4") (class "Default")
      (node (ref "P15") (pin "2") (pinfunction "2_2") (pintype "passive"))
      (node (ref "U6") (pin "15") (pinfunction "PF5/FSMC_A5/ADC3_IN15_15") (pintype "passive"))
    )
    (net (code "29") (name "/KEY0") (class "Default")
      (node (ref "S1") (pin "1") (pinfunction "1_1") (pintype "passive"))
      (node (ref "U6") (pin "2") (pinfunction "PE3/TRACED0/FSMC_A19_2") (pintype "passive"))
    )
    (net (code "30") (name "/KEY1") (class "Default")
      (node (ref "S2") (pin "1") (pinfunction "1_1") (pintype "passive"))
      (node (ref "U6") (pin "1") (pinfunction "PE2/TRACECLK/FSMC_A23/ETH_MII_TXD3_1") (pintype "passive"))
    )
    (net (code "31") (name "/LED1") (class "Default")
      (node (ref "DS1") (pin "2") (pinfunction "K_2") (pintype "passive"))
      (node (ref "U6") (pin "96") (pinfunction "PC6/TIM3_CH1/TIM8_CH1/U6_TX/SDIO_D6/DCMI_D0/I2S2_MCK_96") (pintype "passive"))
    )
    (net (code "32") (name "/LED2") (class "Default")
      (node (ref "DS2") (pin "2") (pinfunction "K_2") (pintype "passive"))
      (node (ref "U6") (pin "97") (pinfunction "PC7/TIM3_CH2/TIM8_CH2/U6_RX/SDIO_D7/DCMI_D1/I2S3_MCK_97") (pintype "passive"))
    )
    (net (code "33") (name "/LED3") (class "Default")
      (node (ref "DS3") (pin "2") (pinfunction "K_2") (pintype "passive"))
      (node (ref "U6") (pin "98") (pinfunction "PC8/TIM3_CH3/TIM8_CH3/U6_CK/SDIO_D0/DCMI_D2_98") (pintype "passive"))
    )
    (net (code "34") (name "/LINK_LED") (class "Default")
      (node (ref "R15") (pin "1") (pintype "passive"))
      (node (ref "RJ3") (pin "12") (pinfunction "LED(Y)_A_12") (pintype "passive"))
      (node (ref "U5") (pin "3") (pinfunction "LED1/REGOFF_3") (pintype "passive"))
    )
    (net (code "35") (name "/PG3") (class "Default")
      (node (ref "P1") (pin "1") (pinfunction "1_1") (pintype "passive"))
      (node (ref "U6") (pin "88") (pinfunction "PG3/FSMC_A13_88") (pintype "passive"))
    )
    (net (code "36") (name "/PG4") (class "Default")
      (node (ref "P1") (pin "2") (pinfunction "2_2") (pintype "passive"))
      (node (ref "U6") (pin "89") (pinfunction "PG4/FSMC_A14_89") (pintype "passive"))
    )
    (net (code "37") (name "/PG5") (class "Default")
      (node (ref "P1") (pin "3") (pinfunction "3_3") (pintype "passive"))
      (node (ref "U6") (pin "90") (pinfunction "PG5/FSMC_A15_90") (pintype "passive"))
    )
    (net (code "38") (name "/PG6") (class "Default")
      (node (ref "P1") (pin "4") (pinfunction "4_4") (pintype "passive"))
      (node (ref "U6") (pin "91") (pinfunction "PG6/FSMC_INT2_91") (pintype "passive"))
    )
    (net (code "39") (name "/PG7") (class "Default")
      (node (ref "P1") (pin "5") (pinfunction "5_5") (pintype "passive"))
      (node (ref "U6") (pin "92") (pinfunction "PG7/FSMC_INT3/U6_CK_92") (pintype "passive"))
    )
    (net (code "40") (name "/PG8") (class "Default")
      (node (ref "P1") (pin "6") (pinfunction "6_6") (pintype "passive"))
      (node (ref "U6") (pin "93") (pinfunction "PG8/U6_RTS/ETH_PPS_OUT_93") (pintype "passive"))
    )
    (net (code "41") (name "/RESET") (class "Default")
      (node (ref "C11") (pin "2") (pinfunction "2_2") (pintype "passive"))
      (node (ref "R5") (pin "1") (pinfunction "1_1") (pintype "passive"))
      (node (ref "U6") (pin "25") (pinfunction "NRST_25") (pintype "passive"))
    )
    (net (code "42") (name "/RMII_CRS_DV") (class "Default")
      (node (ref "U5") (pin "11") (pinfunction "CSR_DV/MODE2_11") (pintype "passive"))
      (node (ref "U6") (pin "43") (pinfunction "PA7/SPI1_MOSI/TIM1_CH1N/TIM3_CH2/TIM8_CH1N/TIM14_CH1/ETH_MII_RX_DV/ETH_RMII_CRS_DV/ADC12_IN7_43") (pintype "passive"))
    )
    (net (code "43") (name "/RMII_REF_CLK") (class "Default")
      (node (ref "U5") (pin "14") (pinfunction "nINT/REFCLKO_14") (pintype "passive"))
      (node (ref "U6") (pin "35") (pinfunction "PA1/U2_RTS/U4_RX/ETH_RMII_REF_CLK/ETH_MII_RX_CLK/TIM2_CH2/TIM5_CH2/ADC123_IN1_35") (pintype "passive"))
    )
    (net (code "44") (name "/RMII_RXD0") (class "Default")
      (node (ref "U5") (pin "8") (pinfunction "RXD0/MODE0_8") (pintype "passive"))
      (node (ref "U6") (pin "44") (pinfunction "PC4/ETH_MII_RXD0/ETH_RMII_RXD0/ADC12_IN14_44") (pintype "passive"))
    )
    (net (code "45") (name "/RMII_RXD1") (class "Default")
      (node (ref "U5") (pin "7") (pinfunction "RXD1/MODE1_7") (pintype "passive"))
      (node (ref "U6") (pin "45") (pinfunction "PC5/ETH_MII_RXD1/ETH_RMII_RXD1/ADC12_IN15_45") (pintype "passive"))
    )
    (net (code "46") (name "/RMII_TXD0") (class "Default")
      (node (ref "U5") (pin "17") (pinfunction "TXD0_17") (pintype "passive"))
      (node (ref "U6") (pin "128") (pinfunction "PG13/FSMC_A24/U6_CTS/ETH_MII_TXD0/ETH_RMII_TXD0_128") (pintype "passive"))
    )
    (net (code "47") (name "/RMII_TXD1") (class "Default")
      (node (ref "U5") (pin "18") (pinfunction "TXD1_18") (pintype "passive"))
      (node (ref "U6") (pin "129") (pinfunction "PG14/FSMC_A25/U6_TX/ETH_MII_TXD1/ETH_RMII_TXD1_129") (pintype "passive"))
    )
    (net (code "48") (name "/RMII_TX_EN") (class "Default")
      (node (ref "U5") (pin "16") (pinfunction "TXEN_16") (pintype "passive"))
      (node (ref "U6") (pin "126") (pinfunction "PG11/FSMC_NCE4_2/ETH_MII_TX_EN/ETH_RMII_TX_EN_126") (pintype "passive"))
    )
    (net (code "49") (name "/RS232_RXD") (class "Default")
      (node (ref "D3") (pin "2") (pinfunction "K_2") (pintype "passive"))
      (node (ref "J1") (pin "3") (pinfunction "3_3") (pintype "passive"))
      (node (ref "U1") (pin "8") (pinfunction "R2IN_8") (pintype "passive"))
    )
    (net (code "50") (name "/RS232_TXD") (class "Default")
      (node (ref "D4") (pin "2") (pinfunction "K_2") (pintype "passive"))
      (node (ref "J1") (pin "7") (pinfunction "7_7") (pintype "passive"))
      (node (ref "U1") (pin "7") (pinfunction "T2OUT_7") (pintype "passive"))
    )
    (net (code "51") (name "/SPEED_LED") (class "Default")
      (node (ref "R16") (pin "1") (pintype "passive"))
      (node (ref "RJ3") (pin "9") (pinfunction "LED(G)_A_9") (pintype "passive"))
      (node (ref "U5") (pin "2") (pinfunction "LED2/nINTSEL_2") (pintype "passive"))
    )
    (net (code "52") (name "/SWCLK") (class "Default")
      (node (ref "P6") (pin "2") (pinfunction "2_2") (pintype "passive"))
      (node (ref "U6") (pin "109") (pinfunction "PA14/JTCK_SWCLK_109") (pintype "passive"))
    )
    (net (code "53") (name "/SWDIO") (class "Default")
      (node (ref "P6") (pin "1") (pinfunction "1_1") (pintype "passive"))
      (node (ref "U6") (pin "105") (pinfunction "PA13/JTMS_SWDIO_105") (pintype "passive"))
    )
    (net (code "54") (name "/TPRX+") (class "Default")
      (node (ref "C23") (pin "1") (pinfunction "1_1") (pintype "passive"))
      (node (ref "R13") (pin "1") (pintype "passive"))
      (node (ref "RJ3") (pin "3") (pinfunction "RD+_3") (pintype "passive"))
      (node (ref "U5") (pin "23") (pinfunction "RXP_23") (pintype "passive"))
    )
    (net (code "55") (name "/TPRX-") (class "Default")
      (node (ref "C24") (pin "1") (pinfunction "1_1") (pintype "passive"))
      (node (ref "R14") (pin "1") (pintype "passive"))
      (node (ref "RJ3") (pin "6") (pinfunction "RD-_6") (pintype "passive"))
      (node (ref "U5") (pin "22") (pinfunction "RXN_22") (pintype "passive"))
    )
    (net (code "56") (name "/TPTX+") (class "Default")
      (node (ref "C21") (pin "1") (pinfunction "1_1") (pintype "passive"))
      (node (ref "R11") (pin "1") (pintype "passive"))
      (node (ref "RJ3") (pin "1") (pinfunction "TD+_1") (pintype "passive"))
      (node (ref "U5") (pin "21") (pinfunction "TXP_21") (pintype "passive"))
    )
    (net (code "57") (name "/TPTX-") (class "Default")
      (node (ref "C22") (pin "1") (pinfunction "1_1") (pintype "passive"))
      (node (ref "R12") (pin "1") (pintype "passive"))
      (node (ref "RJ3") (pin "2") (pinfunction "TD-_2") (pintype "passive"))
      (node (ref "U5") (pin "20") (pinfunction "TXN_20") (pintype "passive"))
    )
    (net (code "58") (name "/USART3-232-RX") (class "Default")
      (node (ref "D5") (pin "1") (pinfunction "A_1") (pintype "passive"))
      (node (ref "U6") (pin "70") (pinfunction "PB11/TIM2_CH4/U3_RX/I2C2_SDA/HS_ULPI_D4/ETH_MII_TX_EN/ETH_RMII_TX_EN_70") (pintype "passive"))
    )
    (net (code "59") (name "/USART3-232-TX") (class "Default")
      (node (ref "U1") (pin "10") (pinfunction "T2IN_10") (pintype "passive"))
      (node (ref "U6") (pin "69") (pinfunction "PB10/SPI2_SCK/TIM2_CH3/U3_TX/I2C2_SCL/OTG_HS_ULPI_D3/I2S2_CK_69") (pintype "passive"))
    )
    (net (code "60") (name "/USB_D+") (class "Default")
      (node (ref "R7") (pin "1") (pintype "passive"))
      (node (ref "U6") (pin "104") (pinfunction "PA12/TIM1_ETR/U1_RTS/CAN1_TX/OTG_FS_DP_104") (pintype "passive"))
    )
    (net (code "61") (name "/USB_D-") (class "Default")
      (node (ref "R6") (pin "1") (pintype "passive"))
      (node (ref "U6") (pin "103") (pinfunction "PA11/TIM1_CH4/U1_CTS/CAN1_RX/OTG_FS_DM_103") (pintype "passive"))
    )
    (net (code "62") (name "3.3V") (class "Default")
      (node (ref "BEEP") (pin "1") (pinfunction "P_1") (pintype "passive"))
      (node (ref "C14") (pin "1") (pinfunction "1_1") (pintype "passive"))
      (node (ref "C15") (pin "1") (pinfunction "1_1") (pintype "passive"))
      (node (ref "C16") (pin "2") (pinfunction "2_2") (pintype "passive"))
      (node (ref "C2") (pin "2") (pintype "passive"))
      (node (ref "C25") (pin "2") (pinfunction "2_2") (pintype "passive"))
      (node (ref "C26") (pin "2") (pinfunction "2_2") (pintype "passive"))
      (node (ref "C35") (pin "2") (pintype "passive"))
      (node (ref "C36") (pin "2") (pintype "passive"))
      (node (ref "C37") (pin "2") (pintype "passive"))
      (node (ref "C38") (pin "2") (pintype "passive"))
      (node (ref "C39") (pin "2") (pintype "passive"))
      (node (ref "C40") (pin "2") (pintype "passive"))
      (node (ref "C41") (pin "2") (pintype "passive"))
      (node (ref "C42") (pin "2") (pintype "passive"))
      (node (ref "C43") (pin "2") (pintype "passive"))
      (node (ref "C44") (pin "2") (pintype "passive"))
      (node (ref "C45") (pin "2") (pintype "passive"))
      (node (ref "C46") (pin "2") (pintype "passive"))
      (node (ref "C5") (pin "1") (pintype "passive"))
      (node (ref "L3") (pin "2") (pintype "passive"))
      (node (ref "P6") (pin "4") (pinfunction "4_4") (pintype "passive"))
      (node (ref "R22") (pin "2") (pintype "passive"))
      (node (ref "R23") (pin "2") (pintype "passive"))
      (node (ref "R24") (pin "1") (pinfunction "1_1") (pintype "passive"))
      (node (ref "R26") (pin "1") (pinfunction "1_1") (pintype "passive"))
      (node (ref "R28") (pin "1") (pinfunction "1_1") (pintype "passive"))
      (node (ref "R30") (pin "1") (pinfunction "1_1") (pintype "passive"))
      (node (ref "R31") (pin "2") (pintype "passive"))
      (node (ref "R33") (pin "2") (pintype "passive"))
      (node (ref "R5") (pin "2") (pinfunction "2_2") (pintype "passive"))
      (node (ref "U1") (pin "16") (pinfunction "VCC_16") (pintype "passive"))
      (node (ref "U3") (pin "2") (pinfunction "OUT_2") (pintype "passive"))
      (node (ref "U5") (pin "9") (pinfunction "VDDIO_9") (pintype "passive"))
      (node (ref "U6") (pin "108") (pinfunction "VDD_108") (pintype "passive"))
      (node (ref "U6") (pin "121") (pinfunction "VDD_121") (pintype "passive"))
      (node (ref "U6") (pin "131") (pinfunction "VDD_131") (pintype "passive"))
      (node (ref "U6") (pin "144") (pinfunction "VDD_144") (pintype "passive"))
      (node (ref "U6") (pin "17") (pinfunction "VDD_17") (pintype "passive"))
      (node (ref "U6") (pin "30") (pinfunction "VDD_30") (pintype "passive"))
      (node (ref "U6") (pin "39") (pinfunction "VDD_39") (pintype "passive"))
      (node (ref "U6") (pin "52") (pinfunction "VDD_52") (pintype "passive"))
      (node (ref "U6") (pin "62") (pinfunction "VDD_62") (pintype "passive"))
      (node (ref "U6") (pin "72") (pinfunction "VDD_72") (pintype "passive"))
      (node (ref "U6") (pin "84") (pinfunction "VDD_84") (pintype "passive"))
      (node (ref "U6") (pin "95") (pinfunction "VDD_95") (pintype "passive"))
      (node (ref "U7") (pin "1") (pinfunction "VCC_1") (pintype "passive"))
    )
    (net (code "63") (name "GND") (class "Default")
      (node (ref "BEEP1") (pin "1") (pinfunction "E_1") (pintype "passive"))
      (node (ref "C10") (pin "2") (pintype "passive"))
      (node (ref "C11") (pin "1") (pinfunction "1_1") (pintype "passive"))
      (node (ref "C12") (pin "1") (pinfunction "1_1") (pintype "passive"))
      (node (ref "C13") (pin "2") (pinfunction "2_2") (pintype "passive"))
      (node (ref "C14") (pin "2") (pinfunction "2_2") (pintype "passive"))
      (node (ref "C15") (pin "2") (pinfunction "2_2") (pintype "passive"))
      (node (ref "C16") (pin "1") (pinfunction "1_1") (pintype "passive"))
      (node (ref "C17") (pin "1") (pinfunction "1_1") (pintype "passive"))
      (node (ref "C18") (pin "1") (pintype "passive"))
      (node (ref "C19") (pin "1") (pintype "passive"))
      (node (ref "C20") (pin "2") (pinfunction "2_2") (pintype "passive"))
      (node (ref "C21") (pin "2") (pinfunction "2_2") (pintype "passive"))
      (node (ref "C22") (pin "2") (pinfunction "2_2") (pintype "passive"))
      (node (ref "C23") (pin "2") (pinfunction "2_2") (pintype "passive"))
      (node (ref "C24") (pin "2") (pinfunction "2_2") (pintype "passive"))
      (node (ref "C25") (pin "1") (pinfunction "1_1") (pintype "passive"))
      (node (ref "C26") (pin "1") (pinfunction "1_1") (pintype "passive"))
      (node (ref "C27") (pin "1") (pintype "passive"))
      (node (ref "C28") (pin "1") (pintype "passive"))
      (node (ref "C29") (pin "2") (pintype "passive"))
      (node (ref "C30") (pin "2") (pintype "passive"))
      (node (ref "C31") (pin "1") (pintype "passive"))
      (node (ref "C32") (pin "1") (pintype "passive"))
      (node (ref "C33") (pin "2") (pintype "passive"))
      (node (ref "C34") (pin "2") (pintype "passive"))
      (node (ref "C35") (pin "1") (pintype "passive"))
      (node (ref "C36") (pin "1") (pintype "passive"))
      (node (ref "C37") (pin "1") (pintype "passive"))
      (node (ref "C38") (pin "1") (pintype "passive"))
      (node (ref "C39") (pin "1") (pintype "passive"))
      (node (ref "C40") (pin "1") (pintype "passive"))
      (node (ref "C41") (pin "1") (pintype "passive"))
      (node (ref "C42") (pin "1") (pintype "passive"))
      (node (ref "C43") (pin "1") (pintype "passive"))
      (node (ref "C44") (pin "1") (pintype "passive"))
      (node (ref "C45") (pin "1") (pintype "passive"))
      (node (ref "C46") (pin "1") (pintype "passive"))
      (node (ref "C5") (pin "2") (pintype "passive"))
      (node (ref "C6") (pin "1") (pinfunction "1_1") (pintype "passive"))
      (node (ref "C7") (pin "2") (pinfunction "2_2") (pintype "passive"))
      (node (ref "C8") (pin "2") (pinfunction "2_2") (pintype "passive"))
      (node (ref "C9") (pin "1") (pinfunction "1_1") (pintype "passive"))
      (node (ref "D10") (pin "1") (pinfunction "A_1") (pintype "passive"))
      (node (ref "D11") (pin "1") (pinfunction "A_1") (pintype "passive"))
      (node (ref "D11") (pin "2") (pinfunction "K_2") (pintype "passive"))
      (node (ref "D2") (pin "1") (pinfunction "A_1") (pintype "passive"))
      (node (ref "D3") (pin "1") (pinfunction "A_1") (pintype "passive"))
      (node (ref "D4") (pin "1") (pinfunction "A_1") (pintype "passive"))
      (node (ref "D6") (pin "1") (pinfunction "A_1") (pintype "passive"))
      (node (ref "D7") (pin "1") (pinfunction "A_1") (pintype "passive"))
      (node (ref "D7") (pin "2") (pinfunction "K_2") (pintype "passive"))
      (node (ref "D8") (pin "1") (pinfunction "A_1") (pintype "passive"))
      (node (ref "D9") (pin "1") (pinfunction "A_1") (pintype "passive"))
      (node (ref "DS4") (pin "2") (pinfunction "K_2") (pintype "passive"))
      (node (ref "J1") (pin "10") (pinfunction "MH1_10") (pintype "passive"))
      (node (ref "J1") (pin "11") (pinfunction "MH2_11") (pintype "passive"))
      (node (ref "J1") (pin "5") (pinfunction "5_5") (pintype "passive"))
      (node (ref "J2") (pin "5") (pinfunction "GND_5") (pintype "passive"))
      (node (ref "J2") (pin "6") (pinfunction "NOP_6") (pintype "passive"))
      (node (ref "J2") (pin "7") (pinfunction "NOP_7") (pintype "passive"))
      (node (ref "P10") (pin "5") (pinfunction "5_5") (pintype "passive"))
      (node (ref "P11") (pin "5") (pinfunction "5_5") (pintype "passive"))
      (node (ref "P12") (pin "3") (pinfunction "3_3") (pintype "passive"))
      (node (ref "P13") (pin "3") (pinfunction "3_3") (pintype "passive"))
      (node (ref "P14") (pin "3") (pinfunction "3_3") (pintype "passive"))
      (node (ref "P15") (pin "3") (pinfunction "3_3") (pintype "passive"))
      (node (ref "P2") (pin "1") (pinfunction "1_1") (pintype "passive"))
      (node (ref "P3") (pin "1") (pinfunction "1_1") (pintype "passive"))
      (node (ref "P4") (pin "1") (pinfunction "1_1") (pintype "passive"))
      (node (ref "P5") (pin "1") (pinfunction "1_1") (pintype "passive"))
      (node (ref "P6") (pin "3") (pinfunction "3_3") (pintype "passive"))
      (node (ref "P7") (pin "5") (pinfunction "5_5") (pintype "passive"))
      (node (ref "P8") (pin "5") (pinfunction "5_5") (pintype "passive"))
      (node (ref "P9") (pin "5") (pinfunction "5_5") (pintype "passive"))
      (node (ref "R1") (pin "1") (pinfunction "1_1") (pintype "passive"))
      (node (ref "R1") (pin "2") (pinfunction "2_2") (pintype "passive"))
      (node (ref "R15") (pin "2") (pintype "passive"))
      (node (ref "R16") (pin "2") (pintype "passive"))
      (node (ref "R17") (pin "1") (pintype "passive"))
      (node (ref "R18") (pin "1") (pintype "passive"))
      (node (ref "R2") (pin "1") (pinfunction "1_1") (pintype "passive"))
      (node (ref "R20") (pin "2") (pinfunction "2_2") (pintype "passive"))
      (node (ref "R21") (pin "2") (pinfunction "2_2") (pintype "passive"))
      (node (ref "R29") (pin "1") (pintype "passive"))
      (node (ref "R32") (pin "1") (pinfunction "1_1") (pintype "passive"))
      (node (ref "R4") (pin "1") (pinfunction "1_1") (pintype "passive"))
      (node (ref "RJ1") (pin "10") (pinfunction "S_10") (pintype "passive"))
      (node (ref "RJ1") (pin "9") (pinfunction "S_9") (pintype "passive"))
      (node (ref "RJ2") (pin "10") (pinfunction "S_10") (pintype "passive"))
      (node (ref "RJ2") (pin "9") (pinfunction "S_9") (pintype "passive"))
      (node (ref "RJ3") (pin "13") (pinfunction "SHILED_13") (pintype "passive"))
      (node (ref "RJ3") (pin "14") (pinfunction "SHILED_14") (pintype "passive"))
      (node (ref "RJ3") (pin "8") (pinfunction "CHS_GND_8") (pintype "passive"))
      (node (ref "S1") (pin "2") (pinfunction "2_2") (pintype "passive"))
      (node (ref "S2") (pin "2") (pinfunction "2_2") (pintype "passive"))
      (node (ref "U1") (pin "15") (pinfunction "GND_15") (pintype "passive"))
      (node (ref "U2") (pin "0") (pinfunction "0_0") (pintype "passive"))
      (node (ref "U2") (pin "3") (pinfunction "GND_3") (pintype "passive"))
      (node (ref "U2") (pin "5") (pinfunction "ON/OFF_5") (pintype "passive"))
      (node (ref "U3") (pin "1") (pinfunction "GND_1") (pintype "passive"))
      (node (ref "U4") (pin "0") (pinfunction "0_0") (pintype "passive"))
      (node (ref "U4") (pin "3") (pinfunction "GND_3") (pintype "passive"))
      (node (ref "U4") (pin "5") (pinfunction "ON/OFF_5") (pintype "passive"))
      (node (ref "U6") (pin "107") (pinfunction "VSS_107") (pintype "passive"))
      (node (ref "U6") (pin "120") (pinfunction "VSS_120") (pintype "passive"))
      (node (ref "U6") (pin "130") (pinfunction "VSS_130") (pintype "passive"))
      (node (ref "U6") (pin "16") (pinfunction "VSS_16") (pintype "passive"))
      (node (ref "U6") (pin "31") (pinfunction "VSSA_31") (pintype "passive"))
      (node (ref "U6") (pin "38") (pinfunction "VSS_38") (pintype "passive"))
      (node (ref "U6") (pin "51") (pinfunction "VSS_51") (pintype "passive"))
      (node (ref "U6") (pin "61") (pinfunction "VSS_61") (pintype "passive"))
      (node (ref "U6") (pin "83") (pinfunction "VSS_83") (pintype "passive"))
      (node (ref "U6") (pin "94") (pinfunction "VSS_94") (pintype "passive"))
      (node (ref "U7") (pin "8") (pinfunction "GND_8") (pintype "passive"))
      (node (ref "U8") (pin "2") (pinfunction "GND_2") (pintype "power_in"))
      (node (ref "U8") (pin "8") (pinfunction "RS_8") (pintype "input"))
      (node (ref "U9") (pin "2") (pinfunction "GND_2") (pintype "power_in"))
      (node (ref "U9") (pin "8") (pinfunction "RS_8") (pintype "input"))
      (node (ref "via1") (pin "1") (pinfunction "0_1") (pintype "passive"))
      (node (ref "via2") (pin "1") (pinfunction "0_1") (pintype "passive"))
      (node (ref "via3") (pin "1") (pinfunction "0_1") (pintype "passive"))
      (node (ref "via4") (pin "1") (pinfunction "0_1") (pintype "passive"))
    )
    (net (code "64") (name "Net-(BEEP-G)") (class "Default")
      (node (ref "BEEP") (pin "2") (pinfunction "G_2") (pintype "passive"))
      (node (ref "BEEP1") (pin "3") (pinfunction "C_3") (pintype "passive"))
    )
    (net (code "65") (name "Net-(BEEP1-B)") (class "Default")
      (node (ref "BEEP1") (pin "2") (pinfunction "B_2") (pintype "passive"))
      (node (ref "R27") (pin "2") (pintype "passive"))
      (node (ref "R29") (pin "2") (pintype "passive"))
    )
    (net (code "66") (name "Net-(D1-A)") (class "Default")
      (node (ref "C6") (pin "2") (pinfunction "2_2") (pintype "passive"))
      (node (ref "C7") (pin "1") (pinfunction "1_1") (pintype "passive"))
      (node (ref "D1") (pin "1") (pinfunction "A_1") (pintype "passive"))
      (node (ref "D2") (pin "2") (pinfunction "K_2") (pintype "passive"))
      (node (ref "F1") (pin "2") (pinfunction "2_2") (pintype "passive"))
    )
    (net (code "67") (name "Net-(D1-K)") (class "Default")
      (node (ref "D1") (pin "2") (pinfunction "K_2") (pintype "passive"))
      (node (ref "U2") (pin "1") (pinfunction "VIN_1") (pintype "passive"))
    )
    (net (code "68") (name "Net-(D5-K)") (class "Default")
      (node (ref "D5") (pin "2") (pinfunction "K_2") (pintype "passive"))
      (node (ref "U1") (pin "9") (pinfunction "R2OUT_9") (pintype "passive"))
    )
    (net (code "69") (name "Net-(D6-K)") (class "Default")
      (node (ref "D6") (pin "2") (pinfunction "K_2") (pintype "passive"))
      (node (ref "L1") (pin "1") (pinfunction "1_1") (pintype "passive"))
      (node (ref "U2") (pin "2") (pinfunction "OUT_2") (pintype "passive"))
    )
    (net (code "70") (name "Net-(D8-K)") (class "Default")
      (node (ref "D8") (pin "2") (pinfunction "K_2") (pintype "passive"))
      (node (ref "L2") (pin "1") (pinfunction "1_1") (pintype "passive"))
      (node (ref "U4") (pin "2") (pinfunction "OUT_2") (pintype "passive"))
    )
    (net (code "71") (name "Net-(D10-K)") (class "Default")
      (node (ref "D10") (pin "2") (pinfunction "K_2") (pintype "passive"))
      (node (ref "D9") (pin "2") (pinfunction "K_2") (pintype "passive"))
      (node (ref "J2") (pin "2") (pinfunction "D-_2") (pintype "passive"))
      (node (ref "J2") (pin "3") (pinfunction "D+_3") (pintype "passive"))
      (node (ref "R6") (pin "2") (pintype "passive"))
      (node (ref "R7") (pin "2") (pintype "passive"))
    )
    (net (code "72") (name "Net-(DS1-A)") (class "Default")
      (node (ref "DS1") (pin "1") (pinfunction "A_1") (pintype "passive"))
      (node (ref "R24") (pin "2") (pinfunction "2_2") (pintype "passive"))
    )
    (net (code "73") (name "Net-(DS2-A)") (class "Default")
      (node (ref "DS2") (pin "1") (pinfunction "A_1") (pintype "passive"))
      (node (ref "R26") (pin "2") (pinfunction "2_2") (pintype "passive"))
    )
    (net (code "74") (name "Net-(DS3-A)") (class "Default")
      (node (ref "DS3") (pin "1") (pinfunction "A_1") (pintype "passive"))
      (node (ref "R28") (pin "2") (pinfunction "2_2") (pintype "passive"))
    )
    (net (code "75") (name "Net-(DS4-A)") (class "Default")
      (node (ref "DS4") (pin "1") (pinfunction "A_1") (pintype "passive"))
      (node (ref "R30") (pin "2") (pinfunction "2_2") (pintype "passive"))
    )
    (net (code "76") (name "Net-(RJ3-LED(G)_K)") (class "Default")
      (node (ref "R21") (pin "1") (pinfunction "1_1") (pintype "passive"))
      (node (ref "RJ3") (pin "10") (pinfunction "LED(G)_K_10") (pintype "passive"))
    )
    (net (code "77") (name "Net-(RJ3-LED(Y)_K)") (class "Default")
      (node (ref "R20") (pin "1") (pinfunction "1_1") (pintype "passive"))
      (node (ref "RJ3") (pin "11") (pinfunction "LED(Y)_K_11") (pintype "passive"))
    )
    (net (code "78") (name "Net-(U1-C1+)") (class "Default")
      (node (ref "C3") (pin "2") (pintype "passive"))
      (node (ref "U1") (pin "1") (pinfunction "C1+_1") (pintype "passive"))
    )
    (net (code "79") (name "Net-(U1-C1-)") (class "Default")
      (node (ref "C3") (pin "1") (pintype "passive"))
      (node (ref "U1") (pin "3") (pinfunction "C1-_3") (pintype "passive"))
    )
    (net (code "80") (name "Net-(U1-C2+)") (class "Default")
      (node (ref "C4") (pin "1") (pintype "passive"))
      (node (ref "U1") (pin "4") (pinfunction "C2+_4") (pintype "passive"))
    )
    (net (code "81") (name "Net-(U1-C2-)") (class "Default")
      (node (ref "C4") (pin "2") (pintype "passive"))
      (node (ref "U1") (pin "5") (pinfunction "C2-_5") (pintype "passive"))
    )
    (net (code "82") (name "Net-(U1-VDD)") (class "Default")
      (node (ref "C2") (pin "1") (pintype "passive"))
      (node (ref "U1") (pin "2") (pinfunction "VDD_2") (pintype "passive"))
    )
    (net (code "83") (name "Net-(U1-VEE)") (class "Default")
      (node (ref "C10") (pin "1") (pintype "passive"))
      (node (ref "U1") (pin "6") (pinfunction "VEE_6") (pintype "passive"))
    )
    (net (code "84") (name "Net-(U2-FB)") (class "Default")
      (node (ref "C1") (pin "1") (pinfunction "1_1") (pintype "passive"))
      (node (ref "R2") (pin "2") (pinfunction "2_2") (pintype "passive"))
      (node (ref "R3") (pin "1") (pinfunction "1_1") (pintype "passive"))
      (node (ref "U2") (pin "4") (pinfunction "FB_4") (pintype "passive"))
    )
    (net (code "85") (name "Net-(U5-MDIO)") (class "Default")
      (node (ref "R10") (pin "2") (pintype "passive"))
      (node (ref "U5") (pin "12") (pinfunction "MDIO_12") (pintype "passive"))
    )
    (net (code "86") (name "Net-(U5-RBIAS)") (class "Default")
      (node (ref "R18") (pin "2") (pintype "passive"))
      (node (ref "U5") (pin "24") (pinfunction "RBIAS_24") (pintype "passive"))
    )
    (net (code "87") (name "Net-(U5-XTAL1{slash}CLKIN)") (class "Default")
      (node (ref "C18") (pin "2") (pintype "passive"))
      (node (ref "R19") (pin "2") (pintype "passive"))
      (node (ref "U5") (pin "5") (pinfunction "XTAL1/CLKIN_5") (pintype "passive"))
      (node (ref "Y1") (pin "1") (pinfunction "OSC1_1") (pintype "passive"))
    )
    (net (code "88") (name "Net-(U5-XTAL2)") (class "Default")
      (node (ref "C19") (pin "2") (pintype "passive"))
      (node (ref "R19") (pin "1") (pintype "passive"))
      (node (ref "U5") (pin "4") (pinfunction "XTAL2_4") (pintype "passive"))
      (node (ref "Y1") (pin "2") (pinfunction "OSC2_2") (pintype "passive"))
    )
    (net (code "89") (name "Net-(U6-PDR_ON)") (class "Default")
      (node (ref "R33") (pin "1") (pintype "passive"))
      (node (ref "U6") (pin "143") (pinfunction "PDR_ON_143") (pintype "passive"))
    )
    (net (code "90") (name "Net-(U6-PH0-OSC_IN)") (class "Default")
      (node (ref "C27") (pin "2") (pintype "passive"))
      (node (ref "R25") (pin "2") (pintype "passive"))
      (node (ref "U6") (pin "23") (pinfunction "PH0-OSC_IN_23") (pintype "passive"))
      (node (ref "Y2") (pin "1") (pinfunction "OSC1_1") (pintype "passive"))
    )
    (net (code "91") (name "Net-(U6-PH1-OSC_OUT)") (class "Default")
      (node (ref "C28") (pin "2") (pintype "passive"))
      (node (ref "R25") (pin "1") (pintype "passive"))
      (node (ref "U6") (pin "24") (pinfunction "PH1-OSC_OUT_24") (pintype "passive"))
      (node (ref "Y2") (pin "2") (pinfunction "OSC2_2") (pintype "passive"))
    )
    (net (code "92") (name "Net-(U6-VDDA)") (class "Default")
      (node (ref "C31") (pin "2") (pintype "passive"))
      (node (ref "C32") (pin "2") (pintype "passive"))
      (node (ref "R31") (pin "1") (pintype "passive"))
      (node (ref "U6") (pin "33") (pinfunction "VDDA_33") (pintype "passive"))
    )
    (net (code "93") (name "Net-(U6-Vcap_1)") (class "Default")
      (node (ref "C29") (pin "1") (pintype "passive"))
      (node (ref "U6") (pin "71") (pinfunction "Vcap_1_71") (pintype "passive"))
    )
    (net (code "94") (name "Net-(U6-Vcap_2)") (class "Default")
      (node (ref "C30") (pin "1") (pintype "passive"))
      (node (ref "U6") (pin "106") (pinfunction "Vcap_2_106") (pintype "passive"))
    )
    (net (code "95") (name "Net-(U8-CANH)") (class "Default")
      (node (ref "R34") (pin "1") (pintype "passive"))
      (node (ref "RJ1") (pin "1") (pinfunction "1_1") (pintype "passive"))
      (node (ref "U8") (pin "7") (pinfunction "CANH_7") (pintype "bidirectional"))
    )
    (net (code "96") (name "Net-(U8-CANL)") (class "Default")
      (node (ref "R34") (pin "2") (pintype "passive"))
      (node (ref "RJ1") (pin "2") (pinfunction "2_2") (pintype "passive"))
      (node (ref "U8") (pin "6") (pinfunction "CANL_6") (pintype "bidirectional"))
    )
    (net (code "97") (name "Net-(U9-CANH)") (class "Default")
      (node (ref "R35") (pin "1") (pintype "passive"))
      (node (ref "RJ2") (pin "1") (pinfunction "1_1") (pintype "passive"))
      (node (ref "U9") (pin "7") (pinfunction "CANH_7") (pintype "bidirectional"))
    )
    (net (code "98") (name "Net-(U9-CANL)") (class "Default")
      (node (ref "R35") (pin "2") (pintype "passive"))
      (node (ref "RJ2") (pin "2") (pinfunction "2_2") (pintype "passive"))
      (node (ref "U9") (pin "6") (pinfunction "CANL_6") (pintype "bidirectional"))
    )
    (net (code "99") (name "VCC3.3E") (class "Default")
      (node (ref "C17") (pin "2") (pinfunction "2_2") (pintype "passive"))
      (node (ref "C20") (pin "1") (pinfunction "1_1") (pintype "passive"))
      (node (ref "L3") (pin "1") (pintype "passive"))
      (node (ref "R11") (pin "2") (pintype "passive"))
      (node (ref "R12") (pin "2") (pintype "passive"))
      (node (ref "R13") (pin "2") (pintype "passive"))
      (node (ref "R14") (pin "2") (pintype "passive"))
      (node (ref "RJ3") (pin "4") (pinfunction "TCT_4") (pintype "passive"))
      (node (ref "RJ3") (pin "5") (pinfunction "RCT_5") (pintype "passive"))
      (node (ref "U5") (pin "1") (pinfunction "VDD2A_1") (pintype "passive"))
      (node (ref "U5") (pin "19") (pinfunction "VDD1A_19") (pintype "passive"))
    )
    (net (code "100") (name "unconnected-(J1-Pad1)") (class "Default")
      (node (ref "J1") (pin "1") (pinfunction "1_1") (pintype "passive"))
    )
    (net (code "101") (name "unconnected-(J1-Pad2)") (class "Default")
      (node (ref "J1") (pin "2") (pinfunction "2_2") (pintype "passive"))
    )
    (net (code "102") (name "unconnected-(J1-Pad4)") (class "Default")
      (node (ref "J1") (pin "4") (pinfunction "4_4") (pintype "passive"))
    )
    (net (code "103") (name "unconnected-(J1-Pad6)") (class "Default")
      (node (ref "J1") (pin "6") (pinfunction "6_6") (pintype "passive"))
    )
    (net (code "104") (name "unconnected-(J1-Pad8)") (class "Default")
      (node (ref "J1") (pin "8") (pinfunction "8_8") (pintype "passive"))
    )
    (net (code "105") (name "unconnected-(J1-Pad9)") (class "Default")
      (node (ref "J1") (pin "9") (pinfunction "9_9") (pintype "passive"))
    )
    (net (code "106") (name "unconnected-(J2-ID-Pad4)") (class "Default")
      (node (ref "J2") (pin "4") (pinfunction "ID_4") (pintype "passive+no_connect"))
    )
    (net (code "107") (name "unconnected-(P7-Pad4)") (class "Default")
      (node (ref "P7") (pin "4") (pinfunction "4_4") (pintype "passive+no_connect"))
    )
    (net (code "108") (name "unconnected-(P8-Pad4)") (class "Default")
      (node (ref "P8") (pin "4") (pinfunction "4_4") (pintype "passive+no_connect"))
    )
    (net (code "109") (name "unconnected-(P9-Pad4)") (class "Default")
      (node (ref "P9") (pin "4") (pinfunction "4_4") (pintype "passive+no_connect"))
    )
    (net (code "110") (name "unconnected-(P10-Pad4)") (class "Default")
      (node (ref "P10") (pin "4") (pinfunction "4_4") (pintype "passive+no_connect"))
    )
    (net (code "111") (name "unconnected-(P11-Pad4)") (class "Default")
      (node (ref "P11") (pin "4") (pinfunction "4_4") (pintype "passive+no_connect"))
    )
    (net (code "112") (name "unconnected-(RJ1-Pad3)") (class "Default")
      (node (ref "RJ1") (pin "3") (pinfunction "3_3") (pintype "passive"))
    )
    (net (code "113") (name "unconnected-(RJ1-Pad4)") (class "Default")
      (node (ref "RJ1") (pin "4") (pinfunction "4_4") (pintype "passive"))
    )
    (net (code "114") (name "unconnected-(RJ1-Pad5)") (class "Default")
      (node (ref "RJ1") (pin "5") (pinfunction "5_5") (pintype "passive"))
    )
    (net (code "115") (name "unconnected-(RJ1-Pad6)") (class "Default")
      (node (ref "RJ1") (pin "6") (pinfunction "6_6") (pintype "passive"))
    )
    (net (code "116") (name "unconnected-(RJ1-Pad7)") (class "Default")
      (node (ref "RJ1") (pin "7") (pinfunction "7_7") (pintype "passive"))
    )
    (net (code "117") (name "unconnected-(RJ1-Pad8)") (class "Default")
      (node (ref "RJ1") (pin "8") (pinfunction "8_8") (pintype "passive"))
    )
    (net (code "118") (name "unconnected-(RJ2-Pad3)") (class "Default")
      (node (ref "RJ2") (pin "3") (pinfunction "3_3") (pintype "passive"))
    )
    (net (code "119") (name "unconnected-(RJ2-Pad4)") (class "Default")
      (node (ref "RJ2") (pin "4") (pinfunction "4_4") (pintype "passive"))
    )
    (net (code "120") (name "unconnected-(RJ2-Pad5)") (class "Default")
      (node (ref "RJ2") (pin "5") (pinfunction "5_5") (pintype "passive"))
    )
    (net (code "121") (name "unconnected-(RJ2-Pad6)") (class "Default")
      (node (ref "RJ2") (pin "6") (pinfunction "6_6") (pintype "passive"))
    )
    (net (code "122") (name "unconnected-(RJ2-Pad7)") (class "Default")
      (node (ref "RJ2") (pin "7") (pinfunction "7_7") (pintype "passive"))
    )
    (net (code "123") (name "unconnected-(RJ2-Pad8)") (class "Default")
      (node (ref "RJ2") (pin "8") (pinfunction "8_8") (pintype "passive"))
    )
    (net (code "124") (name "unconnected-(RJ3-NC-Pad7)") (class "Default")
      (node (ref "RJ3") (pin "7") (pinfunction "NC_7") (pintype "passive"))
    )
    (net (code "125") (name "unconnected-(U1-R1IN-Pad13)") (class "Default")
      (node (ref "U1") (pin "13") (pinfunction "R1IN_13") (pintype "passive+no_connect"))
    )
    (net (code "126") (name "unconnected-(U1-R1OUT-Pad12)") (class "Default")
      (node (ref "U1") (pin "12") (pinfunction "R1OUT_12") (pintype "passive+no_connect"))
    )
    (net (code "127") (name "unconnected-(U1-T1IN-Pad11)") (class "Default")
      (node (ref "U1") (pin "11") (pinfunction "T1IN_11") (pintype "passive+no_connect"))
    )
    (net (code "128") (name "unconnected-(U1-T1OUT-Pad14)") (class "Default")
      (node (ref "U1") (pin "14") (pinfunction "T1OUT_14") (pintype "passive"))
    )
    (net (code "129") (name "unconnected-(U5-GND-Pad25)") (class "Default")
      (node (ref "U5") (pin "25") (pinfunction "GND_25") (pintype "passive"))
    )
    (net (code "130") (name "unconnected-(U5-RXER{slash}PHYAD0-Pad10)") (class "Default")
      (node (ref "U5") (pin "10") (pinfunction "RXER/PHYAD0_10") (pintype "passive"))
    )
    (net (code "131") (name "unconnected-(U5-VDDCR-Pad6)") (class "Default")
      (node (ref "U5") (pin "6") (pinfunction "VDDCR_6") (pintype "passive"))
    )
    (net (code "132") (name "unconnected-(U6-PA0-WKUP{slash}U2_CTS{slash}U4_TX{slash}ETH_MII_CRS{slash}TIM2_CH1_ETR{slash}TIM5_CH1{slash}TIM8_ETR{slash}ADC123_IN0-Pad34)") (class "Default")
      (node (ref "U6") (pin "34") (pinfunction "PA0-WKUP/U2_CTS/U4_TX/ETH_MII_CRS/TIM2_CH1_ETR/TIM5_CH1/TIM8_ETR/ADC123_IN0_34") (pintype "passive"))
    )
    (net (code "133") (name "unconnected-(U6-PA4{slash}SPI1_NSS{slash}U2_CK{slash}DCMI_HSYNC{slash}OTG_HS_SOF{slash}I2S3_WS{slash}DAC1_OUT{slash}ADC12_IN4-Pad40)") (class "Default")
      (node (ref "U6") (pin "40") (pinfunction "PA4/SPI1_NSS/U2_CK/DCMI_HSYNC/OTG_HS_SOF/I2S3_WS/DAC1_OUT/ADC12_IN4_40") (pintype "passive"))
    )
    (net (code "134") (name "unconnected-(U6-PA5{slash}SPI1_SCK{slash}OTG_HS_ULPI_CK{slash}TIM2_CH1_ETR{slash}TIM8_CH1N{slash}DAC2_OUT{slash}ADC12_IN5-Pad41)") (class "Default")
      (node (ref "U6") (pin "41") (pinfunction "PA5/SPI1_SCK/OTG_HS_ULPI_CK/TIM2_CH1_ETR/TIM8_CH1N/DAC2_OUT/ADC12_IN5_41") (pintype "passive"))
    )
    (net (code "135") (name "unconnected-(U6-PA6{slash}SPI1_MISO{slash}TIM1_BKIN{slash}TIM3_CH1{slash}TIM8_BKIN{slash}TIM13_CH1{slash}DCMI_PIXCLK{slash}ADC12_IN6-Pad42)") (class "Default")
      (node (ref "U6") (pin "42") (pinfunction "PA6/SPI1_MISO/TIM1_BKIN/TIM3_CH1/TIM8_BKIN/TIM13_CH1/DCMI_PIXCLK/ADC12_IN6_42") (pintype "passive"))
    )
    (net (code "136") (name "unconnected-(U6-PA8{slash}TIM1_CH1{slash}U1_CK{slash}I2C3_SCL{slash}MCO1{slash}OTG_FS_SOF-Pad100)") (class "Default")
      (node (ref "U6") (pin "100") (pinfunction "PA8/TIM1_CH1/U1_CK/I2C3_SCL/MCO1/OTG_FS_SOF_100") (pintype "passive"))
    )
    (net (code "137") (name "unconnected-(U6-PA9{slash}TIM1_CH2{slash}U1_TX{slash}I2C3_SMBA{slash}OTG_FS_VBUS{slash}DCMI_D0-Pad101)") (class "Default")
      (node (ref "U6") (pin "101") (pinfunction "PA9/TIM1_CH2/U1_TX/I2C3_SMBA/OTG_FS_VBUS/DCMI_D0_101") (pintype "passive"))
    )
    (net (code "138") (name "unconnected-(U6-PA10{slash}TIM1_CH3{slash}U1_RX{slash}OTG_FS_ID{slash}DCMI_D1-Pad102)") (class "Default")
      (node (ref "U6") (pin "102") (pinfunction "PA10/TIM1_CH3/U1_RX/OTG_FS_ID/DCMI_D1_102") (pintype "passive"))
    )
    (net (code "139") (name "unconnected-(U6-PA15{slash}JTDI{slash}SPI1_NSS{slash}SPI3_NSS{slash}TIM2_CH1_ETR{slash}I2S3_WS-Pad110)") (class "Default")
      (node (ref "U6") (pin "110") (pinfunction "PA15/JTDI/SPI1_NSS/SPI3_NSS/TIM2_CH1_ETR/I2S3_WS_110") (pintype "passive"))
    )
    (net (code "140") (name "unconnected-(U6-PB0{slash}TIM1_CH2N{slash}TIM3_CH3{slash}TIM8_CH2N{slash}OTG_HS_ULPI_D1{slash}ETH_MII_RXD2{slash}ADC12_IN8-Pad46)") (class "Default")
      (node (ref "U6") (pin "46") (pinfunction "PB0/TIM1_CH2N/TIM3_CH3/TIM8_CH2N/OTG_HS_ULPI_D1/ETH_MII_RXD2/ADC12_IN8_46") (pintype "passive"))
    )
    (net (code "141") (name "unconnected-(U6-PB1{slash}TIM1_CH3N{slash}TIM3_CH4{slash}TIM8_CH3N{slash}OTG_HS_INTN{slash}ETH_MII_RXD3{slash}ADC12_IN9-Pad47)") (class "Default")
      (node (ref "U6") (pin "47") (pinfunction "PB1/TIM1_CH3N/TIM3_CH4/TIM8_CH3N/OTG_HS_INTN/ETH_MII_RXD3/ADC12_IN9_47") (pintype "passive"))
    )
    (net (code "142") (name "unconnected-(U6-PB2{slash}BOOT1-Pad48)") (class "Default")
      (node (ref "U6") (pin "48") (pinfunction "PB2/BOOT1_48") (pintype "passive"))
    )
    (net (code "143") (name "unconnected-(U6-PB3{slash}JTDO{slash}TRACESWO{slash}TIM2_CH2{slash}SPI1_SCK{slash}SPI3_SCK{slash}I2S3_CK-Pad133)") (class "Default")
      (node (ref "U6") (pin "133") (pinfunction "PB3/JTDO/TRACESWO/TIM2_CH2/SPI1_SCK/SPI3_SCK/I2S3_CK_133") (pintype "passive"))
    )
    (net (code "144") (name "unconnected-(U6-PB4{slash}JNTRST{slash}TIM3_CH1{slash}SPI1_MISO{slash}SPI3_MISO{slash}I2S3ext_SD-Pad134)") (class "Default")
      (node (ref "U6") (pin "134") (pinfunction "PB4/JNTRST/TIM3_CH1/SPI1_MISO/SPI3_MISO/I2S3ext_SD_134") (pintype "passive"))
    )
    (net (code "145") (name "unconnected-(U6-PB5{slash}TIM3_CH2{slash}SPI1_MOSI{slash}SPI3_MOSI{slash}CAN2_RX{slash}I2C1_SMBA{slash}OTG_HS_ULPI_D7{slash}ETH_PPS_OUT{slash}DCMI_D10{slash}I2S3_SD-Pad135)") (class "Default")
      (node (ref "U6") (pin "135") (pinfunction "PB5/TIM3_CH2/SPI1_MOSI/SPI3_MOSI/CAN2_RX/I2C1_SMBA/OTG_HS_ULPI_D7/ETH_PPS_OUT/DCMI_D10/I2S3_SD_135") (pintype "passive"))
    )
    (net (code "146") (name "unconnected-(U6-PB6{slash}TIM4_CH1{slash}U1_TX{slash}CAN2_TX{slash}I2C1_SCL{slash}DCMI_D5-Pad136)") (class "Default")
      (node (ref "U6") (pin "136") (pinfunction "PB6/TIM4_CH1/U1_TX/CAN2_TX/I2C1_SCL/DCMI_D5_136") (pintype "passive"))
    )
    (net (code "147") (name "unconnected-(U6-PB7{slash}TIM4_CH2{slash}U1_RX{slash}FSMC_NL{slash}I2C1_SDA{slash}DCMI_VSYNC-Pad137)") (class "Default")
      (node (ref "U6") (pin "137") (pinfunction "PB7/TIM4_CH2/U1_RX/FSMC_NL/I2C1_SDA/DCMI_VSYNC_137") (pintype "passive"))
    )
    (net (code "148") (name "unconnected-(U6-PB8{slash}TIM4_CH3{slash}TIM10_CH1{slash}CAN1_RX{slash}SDIO_D4{slash}ETH_MII_TXD3{slash}I2C1_SCL{slash}DCMI_D6-Pad139)") (class "Default")
      (node (ref "U6") (pin "139") (pinfunction "PB8/TIM4_CH3/TIM10_CH1/CAN1_RX/SDIO_D4/ETH_MII_TXD3/I2C1_SCL/DCMI_D6_139") (pintype "passive"))
    )
    (net (code "149") (name "unconnected-(U6-PB9{slash}TIM4_CH4{slash}TIM11_CH1{slash}CAN1_TX{slash}SDIO_D5{slash}SPI2_NSS{slash}I2C1_SDA{slash}DCMI_D7{slash}I2S2_WS-Pad140)") (class "Default")
      (node (ref "U6") (pin "140") (pinfunction "PB9/TIM4_CH4/TIM11_CH1/CAN1_TX/SDIO_D5/SPI2_NSS/I2C1_SDA/DCMI_D7/I2S2_WS_140") (pintype "passive"))
    )
    (net (code "150") (name "unconnected-(U6-PB14{slash}SPI2_MISO{slash}TIM1_CH2N{slash}TIM8_CH2N{slash}TIM12_CH1{slash}U3_RTS{slash}OTG_HS_DM{slash}I2S2ext_SD-Pad75)") (class "Default")
      (node (ref "U6") (pin "75") (pinfunction "PB14/SPI2_MISO/TIM1_CH2N/TIM8_CH2N/TIM12_CH1/U3_RTS/OTG_HS_DM/I2S2ext_SD_75") (pintype "passive"))
    )
    (net (code "151") (name "unconnected-(U6-PC0{slash}OTG_HS_ULPI_STP{slash}ADC123_IN10-Pad26)") (class "Default")
      (node (ref "U6") (pin "26") (pinfunction "PC0/OTG_HS_ULPI_STP/ADC123_IN10_26") (pintype "passive"))
    )
    (net (code "152") (name "unconnected-(U6-PC2{slash}SPI2_MISO{slash}OTG_HS_ULPI_DIR{slash}ETH_MII_TXD2{slash}I2S2ext_SD{slash}ADC123_IN12-Pad28)") (class "Default")
      (node (ref "U6") (pin "28") (pinfunction "PC2/SPI2_MISO/OTG_HS_ULPI_DIR/ETH_MII_TXD2/I2S2ext_SD/ADC123_IN12_28") (pintype "passive"))
    )
    (net (code "153") (name "unconnected-(U6-PC3{slash}SPI2_MOSI{slash}OTG_HS_ULPI_NXT{slash}ETH_MII_TX_CLK{slash}I2S2_SD{slash}ADC123_IN13-Pad29)") (class "Default")
      (node (ref "U6") (pin "29") (pinfunction "PC3/SPI2_MOSI/OTG_HS_ULPI_NXT/ETH_MII_TX_CLK/I2S2_SD/ADC123_IN13_29") (pintype "passive"))
    )
    (net (code "154") (name "unconnected-(U6-PC10{slash}SPI3_SCK{slash}U3_TX{slash}U4_TX{slash}SDIO_D2{slash}DCMI_D8{slash}I2S3_CK-Pad111)") (class "Default")
      (node (ref "U6") (pin "111") (pinfunction "PC10/SPI3_SCK/U3_TX/U4_TX/SDIO_D2/DCMI_D8/I2S3_CK_111") (pintype "passive"))
    )
    (net (code "155") (name "unconnected-(U6-PC11{slash}SPI3_MISO{slash}U3_RX{slash}U4_RX{slash}SDIO_D3{slash}DCMI_D4{slash}I2S3ext_SD-Pad112)") (class "Default")
      (node (ref "U6") (pin "112") (pinfunction "PC11/SPI3_MISO/U3_RX/U4_RX/SDIO_D3/DCMI_D4/I2S3ext_SD_112") (pintype "passive"))
    )
    (net (code "156") (name "unconnected-(U6-PC12{slash}SPI3_MOSI{slash}U3_CK{slash}U5_TX{slash}SDIO_CK{slash}DCMI_D9{slash}I2S3_SD-Pad113)") (class "Default")
      (node (ref "U6") (pin "113") (pinfunction "PC12/SPI3_MOSI/U3_CK/U5_TX/SDIO_CK/DCMI_D9/I2S3_SD_113") (pintype "passive"))
    )
    (net (code "157") (name "unconnected-(U6-PC13{slash}RTC_AF1-Pad7)") (class "Default")
      (node (ref "U6") (pin "7") (pinfunction "PC13/RTC_AF1_7") (pintype "passive"))
    )
    (net (code "158") (name "unconnected-(U6-PC14-OSC32_IN-Pad8)") (class "Default")
      (node (ref "U6") (pin "8") (pinfunction "PC14-OSC32_IN_8") (pintype "passive"))
    )
    (net (code "159") (name "unconnected-(U6-PC15-OSC32_OUT-Pad9)") (class "Default")
      (node (ref "U6") (pin "9") (pinfunction "PC15-OSC32_OUT_9") (pintype "passive"))
    )
    (net (code "160") (name "unconnected-(U6-PD2{slash}TIM3_ETR{slash}U5_RX{slash}SDIO_CMD{slash}DCMI_D11-Pad116)") (class "Default")
      (node (ref "U6") (pin "116") (pinfunction "PD2/TIM3_ETR/U5_RX/SDIO_CMD/DCMI_D11_116") (pintype "passive"))
    )
    (net (code "161") (name "unconnected-(U6-PD4{slash}FSMC_NOE{slash}U2_RTS-Pad118)") (class "Default")
      (node (ref "U6") (pin "118") (pinfunction "PD4/FSMC_NOE/U2_RTS_118") (pintype "passive"))
    )
    (net (code "162") (name "unconnected-(U6-PD5{slash}FSMC_NWE{slash}U2_TX-Pad119)") (class "Default")
      (node (ref "U6") (pin "119") (pinfunction "PD5/FSMC_NWE/U2_TX_119") (pintype "passive"))
    )
    (net (code "163") (name "unconnected-(U6-PD6{slash}FSMC_NWAIT{slash}U2_RX-Pad122)") (class "Default")
      (node (ref "U6") (pin "122") (pinfunction "PD6/FSMC_NWAIT/U2_RX_122") (pintype "passive"))
    )
    (net (code "164") (name "unconnected-(U6-PD7{slash}FSMC_NE1{slash}FSMC_NCE2{slash}U2_CK-Pad123)") (class "Default")
      (node (ref "U6") (pin "123") (pinfunction "PD7/FSMC_NE1/FSMC_NCE2/U2_CK_123") (pintype "passive"))
    )
    (net (code "165") (name "unconnected-(U6-PE0{slash}TIM4_ETR{slash}FSMC_NBL0{slash}DCMI_D2-Pad141)") (class "Default")
      (node (ref "U6") (pin "141") (pinfunction "PE0/TIM4_ETR/FSMC_NBL0/DCMI_D2_141") (pintype "passive"))
    )
    (net (code "166") (name "unconnected-(U6-PE1{slash}FSMC_NBL1{slash}DCMI_D3-Pad142)") (class "Default")
      (node (ref "U6") (pin "142") (pinfunction "PE1/FSMC_NBL1/DCMI_D3_142") (pintype "passive"))
    )
    (net (code "167") (name "unconnected-(U6-PE4{slash}TRACED1{slash}FSMC_A20{slash}DCMI_D4-Pad3)") (class "Default")
      (node (ref "U6") (pin "3") (pinfunction "PE4/TRACED1/FSMC_A20/DCMI_D4_3") (pintype "passive"))
    )
    (net (code "168") (name "unconnected-(U6-PE5{slash}TRACED2{slash}FSMC_A21{slash}TIM9_CH1{slash}DCMI_D6-Pad4)") (class "Default")
      (node (ref "U6") (pin "4") (pinfunction "PE5/TRACED2/FSMC_A21/TIM9_CH1/DCMI_D6_4") (pintype "passive"))
    )
    (net (code "169") (name "unconnected-(U6-PE6{slash}TRACED3{slash}FSMC_A22{slash}TIM9_CH2{slash}DCMI_D7-Pad5)") (class "Default")
      (node (ref "U6") (pin "5") (pinfunction "PE6/TRACED3/FSMC_A22/TIM9_CH2/DCMI_D7_5") (pintype "passive"))
    )
    (net (code "170") (name "unconnected-(U6-PE7{slash}FSMC_D4{slash}TIM1_ETR-Pad58)") (class "Default")
      (node (ref "U6") (pin "58") (pinfunction "PE7/FSMC_D4/TIM1_ETR_58") (pintype "passive"))
    )
    (net (code "171") (name "unconnected-(U6-PE8{slash}FSMC_D5{slash}TIM1_CH1N-Pad59)") (class "Default")
      (node (ref "U6") (pin "59") (pinfunction "PE8/FSMC_D5/TIM1_CH1N_59") (pintype "passive"))
    )
    (net (code "172") (name "unconnected-(U6-PE9{slash}FSMC_D6{slash}TIM1_CH1-Pad60)") (class "Default")
      (node (ref "U6") (pin "60") (pinfunction "PE9/FSMC_D6/TIM1_CH1_60") (pintype "passive"))
    )
    (net (code "173") (name "unconnected-(U6-PE10{slash}FSMC_D7{slash}TIM1_CH2N-Pad63)") (class "Default")
      (node (ref "U6") (pin "63") (pinfunction "PE10/FSMC_D7/TIM1_CH2N_63") (pintype "passive"))
    )
    (net (code "174") (name "unconnected-(U6-PE11{slash}FSMC_D8{slash}TIM1_CH2-Pad64)") (class "Default")
      (node (ref "U6") (pin "64") (pinfunction "PE11/FSMC_D8/TIM1_CH2_64") (pintype "passive"))
    )
    (net (code "175") (name "unconnected-(U6-PE12{slash}FSMC_D9{slash}TIM1_CH3N-Pad65)") (class "Default")
      (node (ref "U6") (pin "65") (pinfunction "PE12/FSMC_D9/TIM1_CH3N_65") (pintype "passive"))
    )
    (net (code "176") (name "unconnected-(U6-PE13{slash}FSMC_D10{slash}TIM1_CH3-Pad66)") (class "Default")
      (node (ref "U6") (pin "66") (pinfunction "PE13/FSMC_D10/TIM1_CH3_66") (pintype "passive"))
    )
    (net (code "177") (name "unconnected-(U6-PE14{slash}FSMC_D11{slash}TIM1_CH4-Pad67)") (class "Default")
      (node (ref "U6") (pin "67") (pinfunction "PE14/FSMC_D11/TIM1_CH4_67") (pintype "passive"))
    )
    (net (code "178") (name "unconnected-(U6-PE15{slash}FSMC_D12{slash}TIM1_BKIN-Pad68)") (class "Default")
      (node (ref "U6") (pin "68") (pinfunction "PE15/FSMC_D12/TIM1_BKIN_68") (pintype "passive"))
    )
    (net (code "179") (name "unconnected-(U6-PF6{slash}TIM10_CH1{slash}FSMC_NIORD{slash}ADC3_IN4-Pad18)") (class "Default")
      (node (ref "U6") (pin "18") (pinfunction "PF6/TIM10_CH1/FSMC_NIORD/ADC3_IN4_18") (pintype "passive"))
    )
    (net (code "180") (name "unconnected-(U6-PF7{slash}TIM11_CH1{slash}FSMC_NREG{slash}ADC3_IN5-Pad19)") (class "Default")
      (node (ref "U6") (pin "19") (pinfunction "PF7/TIM11_CH1/FSMC_NREG/ADC3_IN5_19") (pintype "passive"))
    )
    (net (code "181") (name "unconnected-(U6-PF8{slash}TIM13_CH1{slash}FSMC_NIOWR{slash}ADC3_IN6-Pad20)") (class "Default")
      (node (ref "U6") (pin "20") (pinfunction "PF8/TIM13_CH1/FSMC_NIOWR/ADC3_IN6_20") (pintype "passive"))
    )
    (net (code "182") (name "unconnected-(U6-PF9{slash}TIM14_CH1{slash}FSMC_CD{slash}ADC3_IN7-Pad21)") (class "Default")
      (node (ref "U6") (pin "21") (pinfunction "PF9/TIM14_CH1/FSMC_CD/ADC3_IN7_21") (pintype "passive"))
    )
    (net (code "183") (name "unconnected-(U6-PF10{slash}FSMC_INTR{slash}ADC3_IN8-Pad22)") (class "Default")
      (node (ref "U6") (pin "22") (pinfunction "PF10/FSMC_INTR/ADC3_IN8_22") (pintype "passive"))
    )
    (net (code "184") (name "unconnected-(U6-PF11{slash}DCMI_D12-Pad49)") (class "Default")
      (node (ref "U6") (pin "49") (pinfunction "PF11/DCMI_D12_49") (pintype "passive"))
    )
    (net (code "185") (name "unconnected-(U6-PF12{slash}FSMC_A6-Pad50)") (class "Default")
      (node (ref "U6") (pin "50") (pinfunction "PF12/FSMC_A6_50") (pintype "passive"))
    )
    (net (code "186") (name "unconnected-(U6-PF13{slash}FSMC_A7-Pad53)") (class "Default")
      (node (ref "U6") (pin "53") (pinfunction "PF13/FSMC_A7_53") (pintype "passive"))
    )
    (net (code "187") (name "unconnected-(U6-PF14{slash}FSMC_A8-Pad54)") (class "Default")
      (node (ref "U6") (pin "54") (pinfunction "PF14/FSMC_A8_54") (pintype "passive"))
    )
    (net (code "188") (name "unconnected-(U6-PF15{slash}FSMC_A9-Pad55)") (class "Default")
      (node (ref "U6") (pin "55") (pinfunction "PF15/FSMC_A9_55") (pintype "passive"))
    )
    (net (code "189") (name "unconnected-(U6-PG0{slash}FSMC_A10-Pad56)") (class "Default")
      (node (ref "U6") (pin "56") (pinfunction "PG0/FSMC_A10_56") (pintype "passive"))
    )
    (net (code "190") (name "unconnected-(U6-PG1{slash}FSMC_A11-Pad57)") (class "Default")
      (node (ref "U6") (pin "57") (pinfunction "PG1/FSMC_A11_57") (pintype "passive"))
    )
    (net (code "191") (name "unconnected-(U6-PG2{slash}FSMC_A12-Pad87)") (class "Default")
      (node (ref "U6") (pin "87") (pinfunction "PG2/FSMC_A12_87") (pintype "passive"))
    )
    (net (code "192") (name "unconnected-(U6-PG9{slash}FSMC_NE2{slash}FSMC_NCE3{slash}U6_RX-Pad124)") (class "Default")
      (node (ref "U6") (pin "124") (pinfunction "PG9/FSMC_NE2/FSMC_NCE3/U6_RX_124") (pintype "passive"))
    )
    (net (code "193") (name "unconnected-(U6-PG10{slash}FSMC_NCE4_1{slash}FSMC_NE3-Pad125)") (class "Default")
      (node (ref "U6") (pin "125") (pinfunction "PG10/FSMC_NCE4_1/FSMC_NE3_125") (pintype "passive"))
    )
    (net (code "194") (name "unconnected-(U6-PG12{slash}FSMC_NE4{slash}U6_RTS-Pad127)") (class "Default")
      (node (ref "U6") (pin "127") (pinfunction "PG12/FSMC_NE4/U6_RTS_127") (pintype "passive"))
    )
    (net (code "195") (name "unconnected-(U6-PG15{slash}U6_CTS{slash}DCMI_D13-Pad132)") (class "Default")
      (node (ref "U6") (pin "132") (pinfunction "PG15/U6_CTS/DCMI_D13_132") (pintype "passive"))
    )
    (net (code "196") (name "unconnected-(U6-VBAT-Pad6)") (class "Default")
      (node (ref "U6") (pin "6") (pinfunction "VBAT_6") (pintype "passive"))
    )
    (net (code "197") (name "unconnected-(U6-Vref+-Pad32)") (class "Default")
      (node (ref "U6") (pin "32") (pinfunction "Vref+_32") (pintype "passive"))
    )
    (net (code "198") (name "unconnected-(U7-D0-Pad2)") (class "Default")
      (node (ref "U7") (pin "2") (pinfunction "D0_2") (pintype "passive+no_connect"))
    )
    (net (code "199") (name "unconnected-(U7-D1-Pad3)") (class "Default")
      (node (ref "U7") (pin "3") (pinfunction "D1_3") (pintype "passive+no_connect"))
    )
    (net (code "200") (name "unconnected-(U7-D2-Pad4)") (class "Default")
      (node (ref "U7") (pin "4") (pinfunction "D2_4") (pintype "passive+no_connect"))
    )
    (net (code "201") (name "unconnected-(U7-D3-Pad5)") (class "Default")
      (node (ref "U7") (pin "5") (pinfunction "D3_5") (pintype "passive+no_connect"))
    )
    (net (code "202") (name "unconnected-(U7-D4-Pad6)") (class "Default")
      (node (ref "U7") (pin "6") (pinfunction "D4_6") (pintype "passive+no_connect"))
    )
    (net (code "203") (name "unconnected-(U7-D5-Pad7)") (class "Default")
      (node (ref "U7") (pin "7") (pinfunction "D5_7") (pintype "passive+no_connect"))
    )
    (net (code "204") (name "unconnected-(U7-RX-Pad13)") (class "Default")
      (node (ref "U7") (pin "13") (pinfunction "RX_13") (pintype "passive+no_connect"))
    )
    (net (code "205") (name "unconnected-(U7-SWCLK-Pad9)") (class "Default")
      (node (ref "U7") (pin "9") (pinfunction "SWCLK_9") (pintype "passive+no_connect"))
    )
    (net (code "206") (name "unconnected-(U7-SWDIO-Pad10)") (class "Default")
      (node (ref "U7") (pin "10") (pinfunction "SWDIO_10") (pintype "passive+no_connect"))
    )
    (net (code "207") (name "unconnected-(U7-TX-Pad14)") (class "Default")
      (node (ref "U7") (pin "14") (pinfunction "TX_14") (pintype "passive+no_connect"))
    )
    (net (code "208") (name "unconnected-(U8-Vref-Pad5)") (class "Default")
      (node (ref "U8") (pin "5") (pinfunction "Vref_5") (pintype "output"))
    )
    (net (code "209") (name "unconnected-(U9-Vref-Pad5)") (class "Default")
      (node (ref "U9") (pin "5") (pinfunction "Vref_5") (pintype "output"))
    )
  )
)
